# Prom21Core.net
KiCad netlist of a schematic drawn in Altium Designer
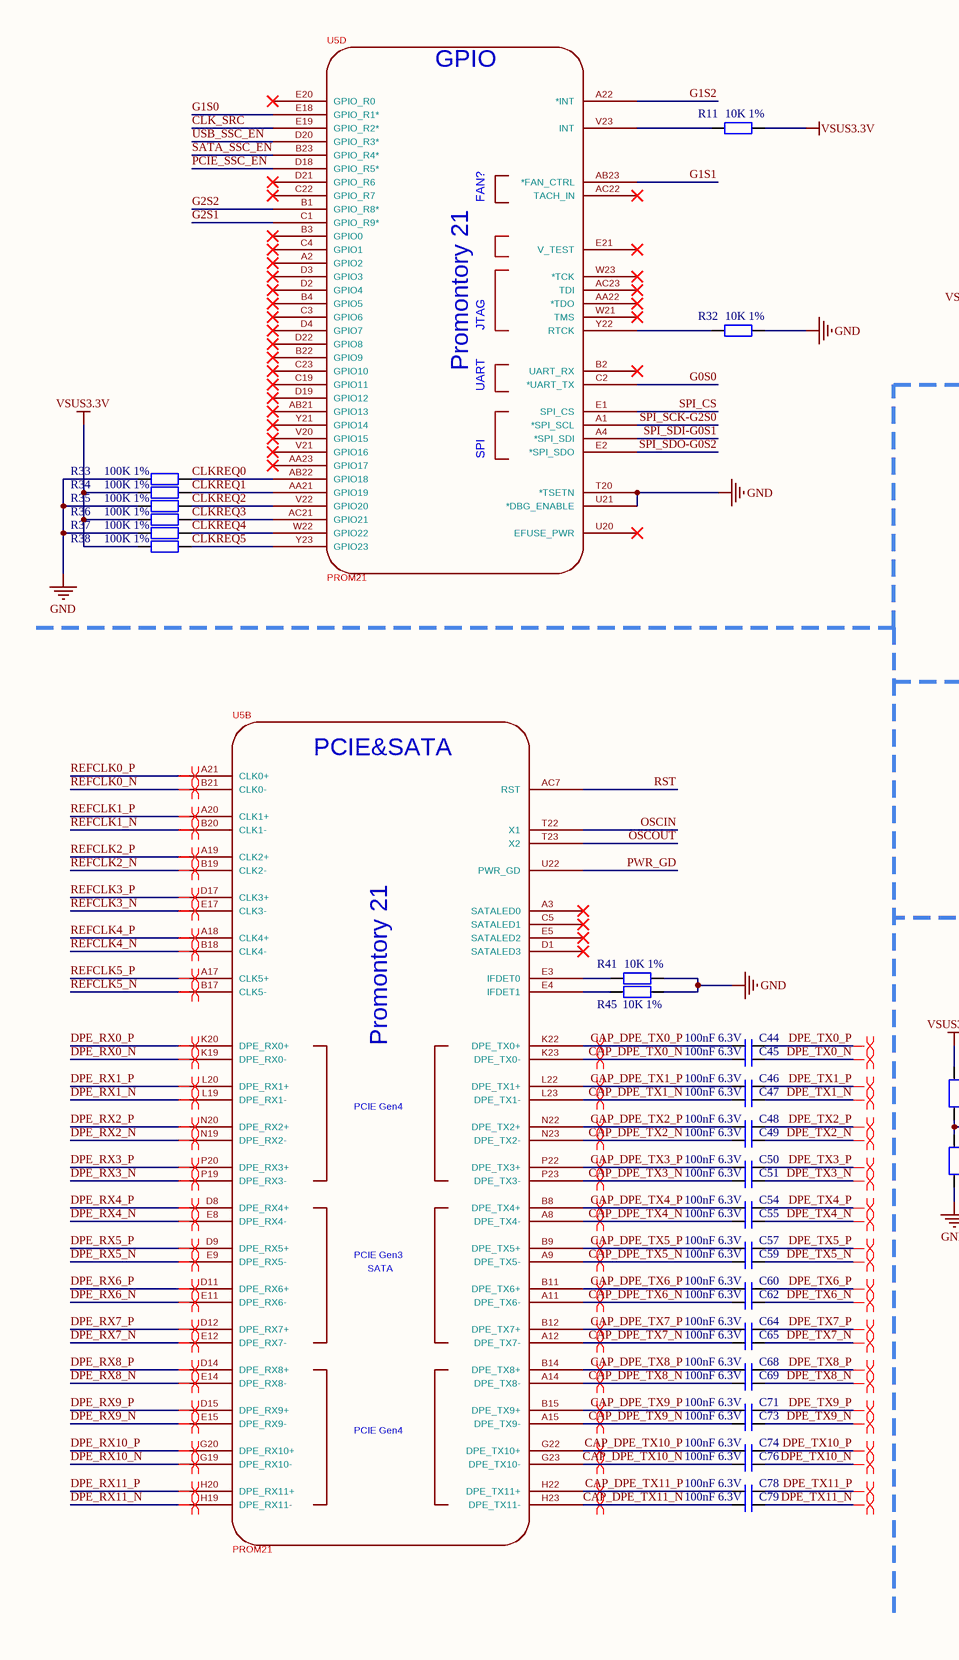
[diagram p0: Prom21Core.SchDoc, left]
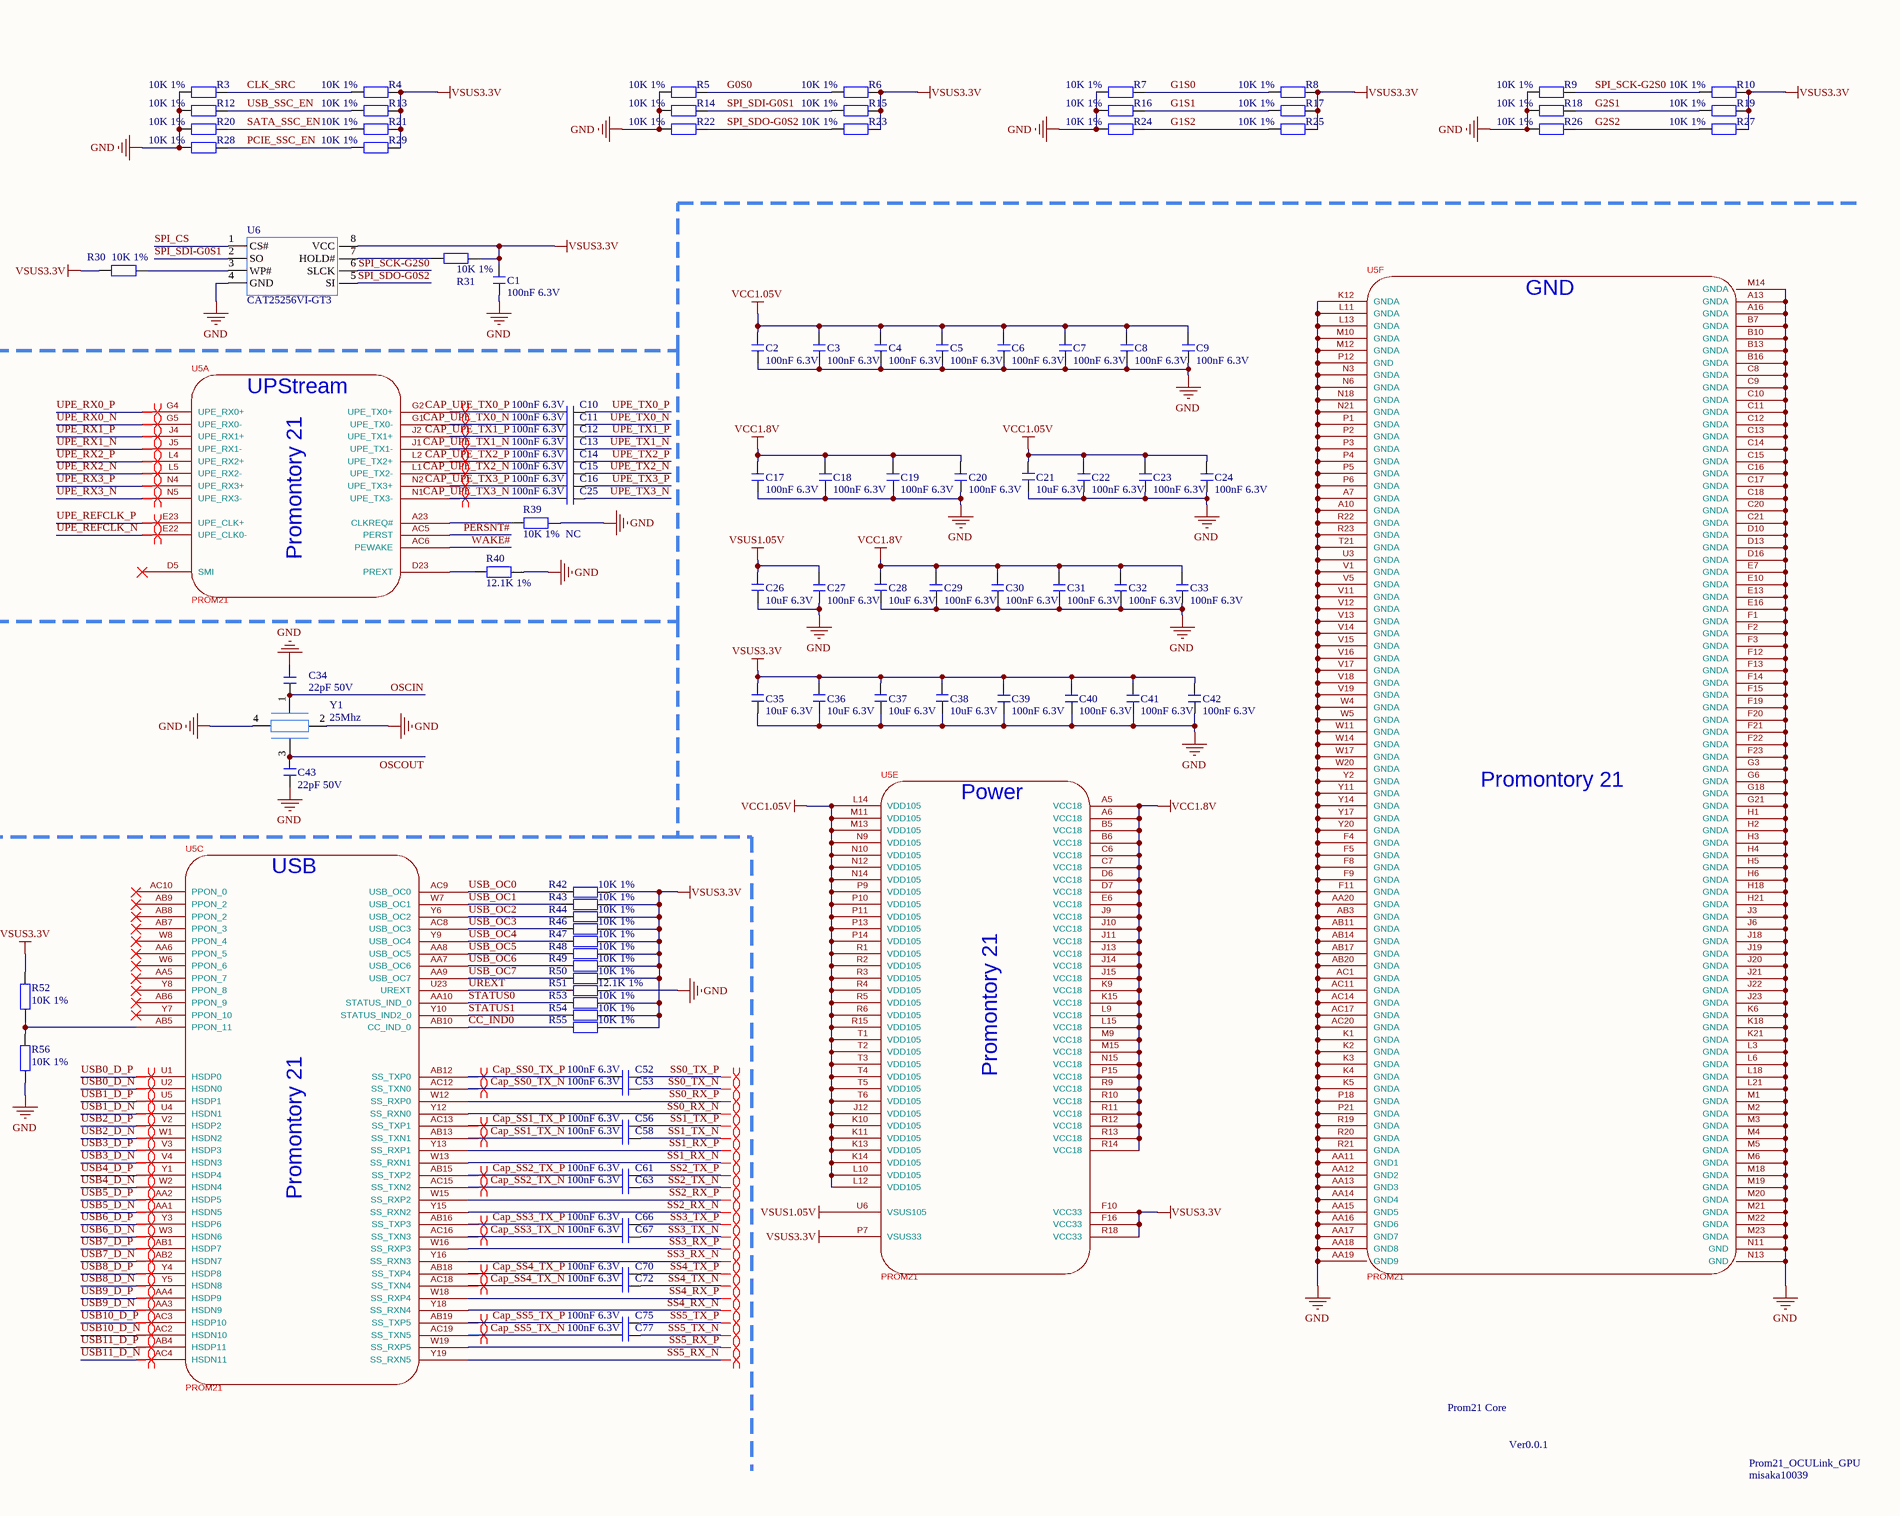
[diagram p1: Prom21Core.SchDoc, right]

(export (version "E")
  (design (tool "Eeschema 10.0.6"))
  (components
    (comp (ref "C1")
      (value "100nF 6.3V")
      (footprint "C0402_L")
      (description "无极性贴片电容")
      (fields (field (name "版权归属") "源创客"))
      (libsource (lib "Capacitor") (part "C"))
    )
    (comp (ref "C2")
      (value "100nF 6.3V")
      (footprint "C0402_L")
      (description "无极性贴片电容")
      (fields (field (name "版权归属") "源创客"))
      (libsource (lib "Capacitor") (part "C"))
    )
    (comp (ref "C3")
      (value "100nF 6.3V")
      (footprint "C0402_L")
      (description "无极性贴片电容")
      (fields (field (name "版权归属") "源创客"))
      (libsource (lib "Capacitor") (part "C"))
    )
    (comp (ref "C4")
      (value "100nF 6.3V")
      (footprint "C0402_L")
      (description "无极性贴片电容")
      (fields (field (name "版权归属") "源创客"))
      (libsource (lib "Capacitor") (part "C"))
    )
    (comp (ref "C5")
      (value "100nF 6.3V")
      (footprint "C0402_L")
      (description "无极性贴片电容")
      (fields (field (name "版权归属") "源创客"))
      (libsource (lib "Capacitor") (part "C"))
    )
    (comp (ref "C6")
      (value "100nF 6.3V")
      (footprint "C0402_L")
      (description "无极性贴片电容")
      (fields (field (name "版权归属") "源创客"))
      (libsource (lib "Capacitor") (part "C"))
    )
    (comp (ref "C7")
      (value "100nF 6.3V")
      (footprint "C0402_L")
      (description "无极性贴片电容")
      (fields (field (name "版权归属") "源创客"))
      (libsource (lib "Capacitor") (part "C"))
    )
    (comp (ref "C8")
      (value "100nF 6.3V")
      (footprint "C0402_L")
      (description "无极性贴片电容")
      (fields (field (name "版权归属") "源创客"))
      (libsource (lib "Capacitor") (part "C"))
    )
    (comp (ref "C9")
      (value "100nF 6.3V")
      (footprint "C0402_L")
      (description "无极性贴片电容")
      (fields (field (name "版权归属") "源创客"))
      (libsource (lib "Capacitor") (part "C"))
    )
    (comp (ref "C10")
      (value "100nF 6.3V")
      (footprint "C0402_L")
      (description "无极性贴片电容")
      (fields (field (name "版权归属") "源创客"))
      (libsource (lib "Capacitor") (part "C"))
    )
    (comp (ref "C11")
      (value "100nF 6.3V")
      (footprint "C0402_L")
      (description "无极性贴片电容")
      (fields (field (name "版权归属") "源创客"))
      (libsource (lib "Capacitor") (part "C"))
    )
    (comp (ref "C12")
      (value "100nF 6.3V")
      (footprint "C0402_L")
      (description "无极性贴片电容")
      (fields (field (name "版权归属") "源创客"))
      (libsource (lib "Capacitor") (part "C"))
    )
    (comp (ref "C13")
      (value "100nF 6.3V")
      (footprint "C0402_L")
      (description "无极性贴片电容")
      (fields (field (name "版权归属") "源创客"))
      (libsource (lib "Capacitor") (part "C"))
    )
    (comp (ref "C14")
      (value "100nF 6.3V")
      (footprint "C0402_L")
      (description "无极性贴片电容")
      (fields (field (name "版权归属") "源创客"))
      (libsource (lib "Capacitor") (part "C"))
    )
    (comp (ref "C15")
      (value "100nF 6.3V")
      (footprint "C0402_L")
      (description "无极性贴片电容")
      (fields (field (name "版权归属") "源创客"))
      (libsource (lib "Capacitor") (part "C"))
    )
    (comp (ref "C16")
      (value "100nF 6.3V")
      (footprint "C0402_L")
      (description "无极性贴片电容")
      (fields (field (name "版权归属") "源创客"))
      (libsource (lib "Capacitor") (part "C"))
    )
    (comp (ref "C17")
      (value "100nF 6.3V")
      (footprint "C0402_L")
      (description "无极性贴片电容")
      (fields (field (name "版权归属") "源创客"))
      (libsource (lib "Capacitor") (part "C"))
    )
    (comp (ref "C18")
      (value "100nF 6.3V")
      (footprint "C0402_L")
      (description "无极性贴片电容")
      (fields (field (name "版权归属") "源创客"))
      (libsource (lib "Capacitor") (part "C"))
    )
    (comp (ref "C19")
      (value "100nF 6.3V")
      (footprint "C0402_L")
      (description "无极性贴片电容")
      (fields (field (name "版权归属") "源创客"))
      (libsource (lib "Capacitor") (part "C"))
    )
    (comp (ref "C20")
      (value "100nF 6.3V")
      (footprint "C0402_L")
      (description "无极性贴片电容")
      (fields (field (name "版权归属") "源创客"))
      (libsource (lib "Capacitor") (part "C"))
    )
    (comp (ref "C21")
      (value "10uF 6.3V")
      (footprint "C0603_L")
      (description "无极性贴片电容")
      (fields (field (name "版权归属") "源创客"))
      (libsource (lib "Capacitor") (part "C"))
    )
    (comp (ref "C22")
      (value "100nF 6.3V")
      (footprint "C0402_L")
      (description "无极性贴片电容")
      (fields (field (name "版权归属") "源创客"))
      (libsource (lib "Capacitor") (part "C"))
    )
    (comp (ref "C23")
      (value "100nF 6.3V")
      (footprint "C0402_L")
      (description "无极性贴片电容")
      (fields (field (name "版权归属") "源创客"))
      (libsource (lib "Capacitor") (part "C"))
    )
    (comp (ref "C24")
      (value "100nF 6.3V")
      (footprint "C0402_L")
      (description "无极性贴片电容")
      (fields (field (name "版权归属") "源创客"))
      (libsource (lib "Capacitor") (part "C"))
    )
    (comp (ref "C25")
      (value "100nF 6.3V")
      (footprint "C0402_L")
      (description "无极性贴片电容")
      (fields (field (name "版权归属") "源创客"))
      (libsource (lib "Capacitor") (part "C"))
    )
    (comp (ref "C26")
      (value "10uF 6.3V")
      (footprint "C0603_L")
      (description "无极性贴片电容")
      (fields (field (name "版权归属") "源创客"))
      (libsource (lib "Capacitor") (part "C"))
    )
    (comp (ref "C27")
      (value "100nF 6.3V")
      (footprint "C0402_L")
      (description "无极性贴片电容")
      (fields (field (name "版权归属") "源创客"))
      (libsource (lib "Capacitor") (part "C"))
    )
    (comp (ref "C28")
      (value "10uF 6.3V")
      (footprint "C0603_L")
      (description "无极性贴片电容")
      (fields (field (name "版权归属") "源创客"))
      (libsource (lib "Capacitor") (part "C"))
    )
    (comp (ref "C29")
      (value "100nF 6.3V")
      (footprint "C0402_L")
      (description "无极性贴片电容")
      (fields (field (name "版权归属") "源创客"))
      (libsource (lib "Capacitor") (part "C"))
    )
    (comp (ref "C30")
      (value "100nF 6.3V")
      (footprint "C0402_L")
      (description "无极性贴片电容")
      (fields (field (name "版权归属") "源创客"))
      (libsource (lib "Capacitor") (part "C"))
    )
    (comp (ref "C31")
      (value "100nF 6.3V")
      (footprint "C0402_L")
      (description "无极性贴片电容")
      (fields (field (name "版权归属") "源创客"))
      (libsource (lib "Capacitor") (part "C"))
    )
    (comp (ref "C32")
      (value "100nF 6.3V")
      (footprint "C0402_L")
      (description "无极性贴片电容")
      (fields (field (name "版权归属") "源创客"))
      (libsource (lib "Capacitor") (part "C"))
    )
    (comp (ref "C33")
      (value "100nF 6.3V")
      (footprint "C0402_L")
      (description "无极性贴片电容")
      (fields (field (name "版权归属") "源创客"))
      (libsource (lib "Capacitor") (part "C"))
    )
    (comp (ref "C34")
      (value "22pF 50V")
      (footprint "C0402_L")
      (description "无极性贴片电容")
      (fields (field (name "版权归属") "源创客"))
      (libsource (lib "Capacitor") (part "C"))
    )
    (comp (ref "C35")
      (value "10uF 6.3V")
      (footprint "C0603_L")
      (description "无极性贴片电容")
      (fields (field (name "版权归属") "源创客"))
      (libsource (lib "Capacitor") (part "C"))
    )
    (comp (ref "C36")
      (value "10uF 6.3V")
      (footprint "C0603_L")
      (description "无极性贴片电容")
      (fields (field (name "版权归属") "源创客"))
      (libsource (lib "Capacitor") (part "C"))
    )
    (comp (ref "C37")
      (value "10uF 6.3V")
      (footprint "C0603_L")
      (description "无极性贴片电容")
      (fields (field (name "版权归属") "源创客"))
      (libsource (lib "Capacitor") (part "C"))
    )
    (comp (ref "C38")
      (value "10uF 6.3V")
      (footprint "C0603_L")
      (description "无极性贴片电容")
      (fields (field (name "版权归属") "源创客"))
      (libsource (lib "Capacitor") (part "C"))
    )
    (comp (ref "C39")
      (value "100nF 6.3V")
      (footprint "C0402_L")
      (description "无极性贴片电容")
      (fields (field (name "版权归属") "源创客"))
      (libsource (lib "Capacitor") (part "C"))
    )
    (comp (ref "C40")
      (value "100nF 6.3V")
      (footprint "C0402_L")
      (description "无极性贴片电容")
      (fields (field (name "版权归属") "源创客"))
      (libsource (lib "Capacitor") (part "C"))
    )
    (comp (ref "C41")
      (value "100nF 6.3V")
      (footprint "C0402_L")
      (description "无极性贴片电容")
      (fields (field (name "版权归属") "源创客"))
      (libsource (lib "Capacitor") (part "C"))
    )
    (comp (ref "C42")
      (value "100nF 6.3V")
      (footprint "C0402_L")
      (description "无极性贴片电容")
      (fields (field (name "版权归属") "源创客"))
      (libsource (lib "Capacitor") (part "C"))
    )
    (comp (ref "C43")
      (value "22pF 50V")
      (footprint "C0402_L")
      (description "无极性贴片电容")
      (fields (field (name "版权归属") "源创客"))
      (libsource (lib "Capacitor") (part "C"))
    )
    (comp (ref "C44")
      (value "100nF 6.3V")
      (footprint "C0402_L")
      (description "无极性贴片电容")
      (fields (field (name "版权归属") "源创客"))
      (libsource (lib "Capacitor") (part "C"))
    )
    (comp (ref "C45")
      (value "100nF 6.3V")
      (footprint "C0402_L")
      (description "无极性贴片电容")
      (fields (field (name "版权归属") "源创客"))
      (libsource (lib "Capacitor") (part "C"))
    )
    (comp (ref "C46")
      (value "100nF 6.3V")
      (footprint "C0402_L")
      (description "无极性贴片电容")
      (fields (field (name "版权归属") "源创客"))
      (libsource (lib "Capacitor") (part "C"))
    )
    (comp (ref "C47")
      (value "100nF 6.3V")
      (footprint "C0402_L")
      (description "无极性贴片电容")
      (fields (field (name "版权归属") "源创客"))
      (libsource (lib "Capacitor") (part "C"))
    )
    (comp (ref "C48")
      (value "100nF 6.3V")
      (footprint "C0402_L")
      (description "无极性贴片电容")
      (fields (field (name "版权归属") "源创客"))
      (libsource (lib "Capacitor") (part "C"))
    )
    (comp (ref "C49")
      (value "100nF 6.3V")
      (footprint "C0402_L")
      (description "无极性贴片电容")
      (fields (field (name "版权归属") "源创客"))
      (libsource (lib "Capacitor") (part "C"))
    )
    (comp (ref "C50")
      (value "100nF 6.3V")
      (footprint "C0402_L")
      (description "无极性贴片电容")
      (fields (field (name "版权归属") "源创客"))
      (libsource (lib "Capacitor") (part "C"))
    )
    (comp (ref "C51")
      (value "100nF 6.3V")
      (footprint "C0402_L")
      (description "无极性贴片电容")
      (fields (field (name "版权归属") "源创客"))
      (libsource (lib "Capacitor") (part "C"))
    )
    (comp (ref "C52")
      (value "100nF 6.3V")
      (footprint "C0402_L")
      (description "无极性贴片电容")
      (fields (field (name "版权归属") "源创客"))
      (libsource (lib "Capacitor") (part "C"))
    )
    (comp (ref "C53")
      (value "100nF 6.3V")
      (footprint "C0402_L")
      (description "无极性贴片电容")
      (fields (field (name "版权归属") "源创客"))
      (libsource (lib "Capacitor") (part "C"))
    )
    (comp (ref "C54")
      (value "100nF 6.3V")
      (footprint "C0402_L")
      (description "无极性贴片电容")
      (fields (field (name "版权归属") "源创客"))
      (libsource (lib "Capacitor") (part "C"))
    )
    (comp (ref "C55")
      (value "100nF 6.3V")
      (footprint "C0402_L")
      (description "无极性贴片电容")
      (fields (field (name "版权归属") "源创客"))
      (libsource (lib "Capacitor") (part "C"))
    )
    (comp (ref "C56")
      (value "100nF 6.3V")
      (footprint "C0402_L")
      (description "无极性贴片电容")
      (fields (field (name "版权归属") "源创客"))
      (libsource (lib "Capacitor") (part "C"))
    )
    (comp (ref "C57")
      (value "100nF 6.3V")
      (footprint "C0402_L")
      (description "无极性贴片电容")
      (fields (field (name "版权归属") "源创客"))
      (libsource (lib "Capacitor") (part "C"))
    )
    (comp (ref "C58")
      (value "100nF 6.3V")
      (footprint "C0402_L")
      (description "无极性贴片电容")
      (fields (field (name "版权归属") "源创客"))
      (libsource (lib "Capacitor") (part "C"))
    )
    (comp (ref "C59")
      (value "100nF 6.3V")
      (footprint "C0402_L")
      (description "无极性贴片电容")
      (fields (field (name "版权归属") "源创客"))
      (libsource (lib "Capacitor") (part "C"))
    )
    (comp (ref "C60")
      (value "100nF 6.3V")
      (footprint "C0402_L")
      (description "无极性贴片电容")
      (fields (field (name "版权归属") "源创客"))
      (libsource (lib "Capacitor") (part "C"))
    )
    (comp (ref "C61")
      (value "100nF 6.3V")
      (footprint "C0402_L")
      (description "无极性贴片电容")
      (fields (field (name "版权归属") "源创客"))
      (libsource (lib "Capacitor") (part "C"))
    )
    (comp (ref "C62")
      (value "100nF 6.3V")
      (footprint "C0402_L")
      (description "无极性贴片电容")
      (fields (field (name "版权归属") "源创客"))
      (libsource (lib "Capacitor") (part "C"))
    )
    (comp (ref "C63")
      (value "100nF 6.3V")
      (footprint "C0402_L")
      (description "无极性贴片电容")
      (fields (field (name "版权归属") "源创客"))
      (libsource (lib "Capacitor") (part "C"))
    )
    (comp (ref "C64")
      (value "100nF 6.3V")
      (footprint "C0402_L")
      (description "无极性贴片电容")
      (fields (field (name "版权归属") "源创客"))
      (libsource (lib "Capacitor") (part "C"))
    )
    (comp (ref "C65")
      (value "100nF 6.3V")
      (footprint "C0402_L")
      (description "无极性贴片电容")
      (fields (field (name "版权归属") "源创客"))
      (libsource (lib "Capacitor") (part "C"))
    )
    (comp (ref "C66")
      (value "100nF 6.3V")
      (footprint "C0402_L")
      (description "无极性贴片电容")
      (fields (field (name "版权归属") "源创客"))
      (libsource (lib "Capacitor") (part "C"))
    )
    (comp (ref "C67")
      (value "100nF 6.3V")
      (footprint "C0402_L")
      (description "无极性贴片电容")
      (fields (field (name "版权归属") "源创客"))
      (libsource (lib "Capacitor") (part "C"))
    )
    (comp (ref "C68")
      (value "100nF 6.3V")
      (footprint "C0402_L")
      (description "无极性贴片电容")
      (fields (field (name "版权归属") "源创客"))
      (libsource (lib "Capacitor") (part "C"))
    )
    (comp (ref "C69")
      (value "100nF 6.3V")
      (footprint "C0402_L")
      (description "无极性贴片电容")
      (fields (field (name "版权归属") "源创客"))
      (libsource (lib "Capacitor") (part "C"))
    )
    (comp (ref "C70")
      (value "100nF 6.3V")
      (footprint "C0402_L")
      (description "无极性贴片电容")
      (fields (field (name "版权归属") "源创客"))
      (libsource (lib "Capacitor") (part "C"))
    )
    (comp (ref "C71")
      (value "100nF 6.3V")
      (footprint "C0402_L")
      (description "无极性贴片电容")
      (fields (field (name "版权归属") "源创客"))
      (libsource (lib "Capacitor") (part "C"))
    )
    (comp (ref "C72")
      (value "100nF 6.3V")
      (footprint "C0402_L")
      (description "无极性贴片电容")
      (fields (field (name "版权归属") "源创客"))
      (libsource (lib "Capacitor") (part "C"))
    )
    (comp (ref "C73")
      (value "100nF 6.3V")
      (footprint "C0402_L")
      (description "无极性贴片电容")
      (fields (field (name "版权归属") "源创客"))
      (libsource (lib "Capacitor") (part "C"))
    )
    (comp (ref "C74")
      (value "100nF 6.3V")
      (footprint "C0402_L")
      (description "无极性贴片电容")
      (fields (field (name "版权归属") "源创客"))
      (libsource (lib "Capacitor") (part "C"))
    )
    (comp (ref "C75")
      (value "100nF 6.3V")
      (footprint "C0402_L")
      (description "无极性贴片电容")
      (fields (field (name "版权归属") "源创客"))
      (libsource (lib "Capacitor") (part "C"))
    )
    (comp (ref "C76")
      (value "100nF 6.3V")
      (footprint "C0402_L")
      (description "无极性贴片电容")
      (fields (field (name "版权归属") "源创客"))
      (libsource (lib "Capacitor") (part "C"))
    )
    (comp (ref "C77")
      (value "100nF 6.3V")
      (footprint "C0402_L")
      (description "无极性贴片电容")
      (fields (field (name "版权归属") "源创客"))
      (libsource (lib "Capacitor") (part "C"))
    )
    (comp (ref "C78")
      (value "100nF 6.3V")
      (footprint "C0402_L")
      (description "无极性贴片电容")
      (fields (field (name "版权归属") "源创客"))
      (libsource (lib "Capacitor") (part "C"))
    )
    (comp (ref "C79")
      (value "100nF 6.3V")
      (footprint "C0402_L")
      (description "无极性贴片电容")
      (fields (field (name "版权归属") "源创客"))
      (libsource (lib "Capacitor") (part "C"))
    )
    (comp (ref "R3")
      (value "10K 1%")
      (footprint "R0402_L")
      (description "贴片电阻")
      (fields (field (name "版权归属") "源创客"))
      (libsource (lib "Resistor") (part "R"))
    )
    (comp (ref "R4")
      (value "10K 1%")
      (footprint "R0402_L")
      (description "贴片电阻")
      (fields (field (name "版权归属") "源创客"))
      (libsource (lib "Resistor") (part "R"))
    )
    (comp (ref "R5")
      (value "10K 1%")
      (footprint "R0402_L")
      (description "贴片电阻")
      (fields (field (name "版权归属") "源创客"))
      (libsource (lib "Resistor") (part "R"))
    )
    (comp (ref "R6")
      (value "10K 1%")
      (footprint "R0402_L")
      (description "贴片电阻")
      (fields (field (name "版权归属") "源创客"))
      (libsource (lib "Resistor") (part "R"))
    )
    (comp (ref "R7")
      (value "10K 1%")
      (footprint "R0402_L")
      (description "贴片电阻")
      (fields (field (name "版权归属") "源创客"))
      (libsource (lib "Resistor") (part "R"))
    )
    (comp (ref "R8")
      (value "10K 1%")
      (footprint "R0402_L")
      (description "贴片电阻")
      (fields (field (name "版权归属") "源创客"))
      (libsource (lib "Resistor") (part "R"))
    )
    (comp (ref "R9")
      (value "10K 1%")
      (footprint "R0402_L")
      (description "贴片电阻")
      (fields (field (name "版权归属") "源创客"))
      (libsource (lib "Resistor") (part "R"))
    )
    (comp (ref "R10")
      (value "10K 1%")
      (footprint "R0402_L")
      (description "贴片电阻")
      (fields (field (name "版权归属") "源创客"))
      (libsource (lib "Resistor") (part "R"))
    )
    (comp (ref "R11")
      (value "10K 1%")
      (footprint "R0402_L")
      (description "贴片电阻")
      (fields (field (name "版权归属") "源创客"))
      (libsource (lib "Resistor") (part "R"))
    )
    (comp (ref "R12")
      (value "10K 1%")
      (footprint "R0402_L")
      (description "贴片电阻")
      (fields (field (name "版权归属") "源创客"))
      (libsource (lib "Resistor") (part "R"))
    )
    (comp (ref "R13")
      (value "10K 1%")
      (footprint "R0402_L")
      (description "贴片电阻")
      (fields (field (name "版权归属") "源创客"))
      (libsource (lib "Resistor") (part "R"))
    )
    (comp (ref "R14")
      (value "10K 1%")
      (footprint "R0402_L")
      (description "贴片电阻")
      (fields (field (name "版权归属") "源创客"))
      (libsource (lib "Resistor") (part "R"))
    )
    (comp (ref "R15")
      (value "10K 1%")
      (footprint "R0402_L")
      (description "贴片电阻")
      (fields (field (name "版权归属") "源创客"))
      (libsource (lib "Resistor") (part "R"))
    )
    (comp (ref "R16")
      (value "10K 1%")
      (footprint "R0402_L")
      (description "贴片电阻")
      (fields (field (name "版权归属") "源创客"))
      (libsource (lib "Resistor") (part "R"))
    )
    (comp (ref "R17")
      (value "10K 1%")
      (footprint "R0402_L")
      (description "贴片电阻")
      (fields (field (name "版权归属") "源创客"))
      (libsource (lib "Resistor") (part "R"))
    )
    (comp (ref "R18")
      (value "10K 1%")
      (footprint "R0402_L")
      (description "贴片电阻")
      (fields (field (name "版权归属") "源创客"))
      (libsource (lib "Resistor") (part "R"))
    )
    (comp (ref "R19")
      (value "10K 1%")
      (footprint "R0402_L")
      (description "贴片电阻")
      (fields (field (name "版权归属") "源创客"))
      (libsource (lib "Resistor") (part "R"))
    )
    (comp (ref "R20")
      (value "10K 1%")
      (footprint "R0402_L")
      (description "贴片电阻")
      (fields (field (name "版权归属") "源创客"))
      (libsource (lib "Resistor") (part "R"))
    )
    (comp (ref "R21")
      (value "10K 1%")
      (footprint "R0402_L")
      (description "贴片电阻")
      (fields (field (name "版权归属") "源创客"))
      (libsource (lib "Resistor") (part "R"))
    )
    (comp (ref "R22")
      (value "10K 1%")
      (footprint "R0402_L")
      (description "贴片电阻")
      (fields (field (name "版权归属") "源创客"))
      (libsource (lib "Resistor") (part "R"))
    )
    (comp (ref "R23")
      (value "10K 1%")
      (footprint "R0402_L")
      (description "贴片电阻")
      (fields (field (name "版权归属") "源创客"))
      (libsource (lib "Resistor") (part "R"))
    )
    (comp (ref "R24")
      (value "10K 1%")
      (footprint "R0402_L")
      (description "贴片电阻")
      (fields (field (name "版权归属") "源创客"))
      (libsource (lib "Resistor") (part "R"))
    )
    (comp (ref "R25")
      (value "10K 1%")
      (footprint "R0402_L")
      (description "贴片电阻")
      (fields (field (name "版权归属") "源创客"))
      (libsource (lib "Resistor") (part "R"))
    )
    (comp (ref "R26")
      (value "10K 1%")
      (footprint "R0402_L")
      (description "贴片电阻")
      (fields (field (name "版权归属") "源创客"))
      (libsource (lib "Resistor") (part "R"))
    )
    (comp (ref "R27")
      (value "10K 1%")
      (footprint "R0402_L")
      (description "贴片电阻")
      (fields (field (name "版权归属") "源创客"))
      (libsource (lib "Resistor") (part "R"))
    )
    (comp (ref "R28")
      (value "10K 1%")
      (footprint "R0402_L")
      (description "贴片电阻")
      (fields (field (name "版权归属") "源创客"))
      (libsource (lib "Resistor") (part "R"))
    )
    (comp (ref "R29")
      (value "10K 1%")
      (footprint "R0402_L")
      (description "贴片电阻")
      (fields (field (name "版权归属") "源创客"))
      (libsource (lib "Resistor") (part "R"))
    )
    (comp (ref "R30")
      (value "10K 1%")
      (footprint "R0402_L")
      (description "贴片电阻")
      (fields (field (name "版权归属") "源创客"))
      (libsource (lib "Resistor") (part "R"))
    )
    (comp (ref "R31")
      (value "10K 1%")
      (footprint "R0402_L")
      (description "贴片电阻")
      (fields (field (name "版权归属") "源创客"))
      (libsource (lib "Resistor") (part "R"))
    )
    (comp (ref "R32")
      (value "10K 1%")
      (footprint "R0402_L")
      (description "贴片电阻")
      (fields (field (name "版权归属") "源创客"))
      (libsource (lib "Resistor") (part "R"))
    )
    (comp (ref "R33")
      (value "100K 1%")
      (footprint "R0402_L")
      (description "贴片电阻")
      (fields (field (name "版权归属") "源创客"))
      (libsource (lib "Resistor") (part "R"))
    )
    (comp (ref "R34")
      (value "100K 1%")
      (footprint "R0402_L")
      (description "贴片电阻")
      (fields (field (name "版权归属") "源创客"))
      (libsource (lib "Resistor") (part "R"))
    )
    (comp (ref "R35")
      (value "100K 1%")
      (footprint "R0402_L")
      (description "贴片电阻")
      (fields (field (name "版权归属") "源创客"))
      (libsource (lib "Resistor") (part "R"))
    )
    (comp (ref "R36")
      (value "100K 1%")
      (footprint "R0402_L")
      (description "贴片电阻")
      (fields (field (name "版权归属") "源创客"))
      (libsource (lib "Resistor") (part "R"))
    )
    (comp (ref "R37")
      (value "100K 1%")
      (footprint "R0402_L")
      (description "贴片电阻")
      (fields (field (name "版权归属") "源创客"))
      (libsource (lib "Resistor") (part "R"))
    )
    (comp (ref "R38")
      (value "100K 1%")
      (footprint "R0402_L")
      (description "贴片电阻")
      (fields (field (name "版权归属") "源创客"))
      (libsource (lib "Resistor") (part "R"))
    )
    (comp (ref "R39")
      (value "10K 1%  NC")
      (footprint "R0402_L")
      (description "贴片电阻")
      (fields (field (name "版权归属") "源创客"))
      (libsource (lib "Resistor") (part "R"))
    )
    (comp (ref "R40")
      (value "12.1K 1%")
      (footprint "R0402_L")
      (description "贴片电阻")
      (fields (field (name "版权归属") "源创客"))
      (libsource (lib "Resistor") (part "R"))
    )
    (comp (ref "R41")
      (value "10K 1%")
      (footprint "R0402_L")
      (description "贴片电阻")
      (fields (field (name "版权归属") "源创客"))
      (libsource (lib "Resistor") (part "R"))
    )
    (comp (ref "R42")
      (value "10K 1%")
      (footprint "R0402_L")
      (description "贴片电阻")
      (fields (field (name "版权归属") "源创客"))
      (libsource (lib "Resistor") (part "R"))
    )
    (comp (ref "R43")
      (value "10K 1%")
      (footprint "R0402_L")
      (description "贴片电阻")
      (fields (field (name "版权归属") "源创客"))
      (libsource (lib "Resistor") (part "R"))
    )
    (comp (ref "R44")
      (value "10K 1%")
      (footprint "R0402_L")
      (description "贴片电阻")
      (fields (field (name "版权归属") "源创客"))
      (libsource (lib "Resistor") (part "R"))
    )
    (comp (ref "R45")
      (value "10K 1%")
      (footprint "R0402_L")
      (description "贴片电阻")
      (fields (field (name "版权归属") "源创客"))
      (libsource (lib "Resistor") (part "R"))
    )
    (comp (ref "R46")
      (value "10K 1%")
      (footprint "R0402_L")
      (description "贴片电阻")
      (fields (field (name "版权归属") "源创客"))
      (libsource (lib "Resistor") (part "R"))
    )
    (comp (ref "R47")
      (value "10K 1%")
      (footprint "R0402_L")
      (description "贴片电阻")
      (fields (field (name "版权归属") "源创客"))
      (libsource (lib "Resistor") (part "R"))
    )
    (comp (ref "R48")
      (value "10K 1%")
      (footprint "R0402_L")
      (description "贴片电阻")
      (fields (field (name "版权归属") "源创客"))
      (libsource (lib "Resistor") (part "R"))
    )
    (comp (ref "R49")
      (value "10K 1%")
      (footprint "R0402_L")
      (description "贴片电阻")
      (fields (field (name "版权归属") "源创客"))
      (libsource (lib "Resistor") (part "R"))
    )
    (comp (ref "R50")
      (value "10K 1%")
      (footprint "R0402_L")
      (description "贴片电阻")
      (fields (field (name "版权归属") "源创客"))
      (libsource (lib "Resistor") (part "R"))
    )
    (comp (ref "R51")
      (value "12.1K 1%")
      (footprint "R0402_L")
      (description "贴片电阻")
      (fields (field (name "版权归属") "源创客"))
      (libsource (lib "Resistor") (part "R"))
    )
    (comp (ref "R52")
      (value "10K 1%")
      (footprint "R0402_L")
      (description "贴片电阻")
      (fields (field (name "版权归属") "源创客"))
      (libsource (lib "Resistor") (part "R"))
    )
    (comp (ref "R53")
      (value "10K 1%")
      (footprint "R0402_L")
      (description "贴片电阻")
      (fields (field (name "版权归属") "源创客"))
      (libsource (lib "Resistor") (part "R"))
    )
    (comp (ref "R54")
      (value "10K 1%")
      (footprint "R0402_L")
      (description "贴片电阻")
      (fields (field (name "版权归属") "源创客"))
      (libsource (lib "Resistor") (part "R"))
    )
    (comp (ref "R55")
      (value "10K 1%")
      (footprint "R0402_L")
      (description "贴片电阻")
      (fields (field (name "版权归属") "源创客"))
      (libsource (lib "Resistor") (part "R"))
    )
    (comp (ref "R56")
      (value "10K 1%")
      (footprint "R0402_L")
      (description "贴片电阻")
      (fields (field (name "版权归属") "源创客"))
      (libsource (lib "Resistor") (part "R"))
    )
    (comp (ref "U5")
      (value "PROM21")
      (footprint "PROM21")
      (description "AMD B650")
      (libsource (lib "Brage") (part "PROM21"))
    )
    (comp (ref "U6") (value "CAT25256VI-GT3") (footprint "SOP8_M") (libsource (lib "Flash") (part "P25D40H")))
    (comp (ref "Y1") (value "25Mhz") (footprint "OSC-3225-4P") (libsource (lib "Crystal") (part "Crystal")))
  )
  (nets
    (net (code "1") (name "/CAP_DPE_TX0_N") (class "Default")
      (node (ref "C45") (pin "2") (pinfunction "2_2") (pintype "passive"))
      (node (ref "U5") (pin "K23") (pinfunction "DPE_TX0-_K23") (pintype "passive"))
    )
    (net (code "2") (name "/CAP_DPE_TX0_P") (class "Default")
      (node (ref "C44") (pin "2") (pinfunction "2_2") (pintype "passive"))
      (node (ref "U5") (pin "K22") (pinfunction "DPE_TX0+_K22") (pintype "passive"))
    )
    (net (code "3") (name "/CAP_DPE_TX1_N") (class "Default")
      (node (ref "C47") (pin "2") (pinfunction "2_2") (pintype "passive"))
      (node (ref "U5") (pin "L23") (pinfunction "DPE_TX1-_L23") (pintype "passive"))
    )
    (net (code "4") (name "/CAP_DPE_TX1_P") (class "Default")
      (node (ref "C46") (pin "2") (pinfunction "2_2") (pintype "passive"))
      (node (ref "U5") (pin "L22") (pinfunction "DPE_TX1+_L22") (pintype "passive"))
    )
    (net (code "5") (name "/CAP_DPE_TX2_N") (class "Default")
      (node (ref "C49") (pin "2") (pinfunction "2_2") (pintype "passive"))
      (node (ref "U5") (pin "N23") (pinfunction "DPE_TX2-_N23") (pintype "passive"))
    )
    (net (code "6") (name "/CAP_DPE_TX2_P") (class "Default")
      (node (ref "C48") (pin "2") (pinfunction "2_2") (pintype "passive"))
      (node (ref "U5") (pin "N22") (pinfunction "DPE_TX2+_N22") (pintype "passive"))
    )
    (net (code "7") (name "/CAP_DPE_TX3_N") (class "Default")
      (node (ref "C51") (pin "2") (pinfunction "2_2") (pintype "passive"))
      (node (ref "U5") (pin "P23") (pinfunction "DPE_TX3-_P23") (pintype "passive"))
    )
    (net (code "8") (name "/CAP_DPE_TX3_P") (class "Default")
      (node (ref "C50") (pin "2") (pinfunction "2_2") (pintype "passive"))
      (node (ref "U5") (pin "P22") (pinfunction "DPE_TX3+_P22") (pintype "passive"))
    )
    (net (code "9") (name "/CAP_DPE_TX4_N") (class "Default")
      (node (ref "C55") (pin "2") (pinfunction "2_2") (pintype "passive"))
      (node (ref "U5") (pin "A8") (pinfunction "DPE_TX4-_A8") (pintype "passive"))
    )
    (net (code "10") (name "/CAP_DPE_TX4_P") (class "Default")
      (node (ref "C54") (pin "2") (pinfunction "2_2") (pintype "passive"))
      (node (ref "U5") (pin "B8") (pinfunction "DPE_TX4+_B8") (pintype "passive"))
    )
    (net (code "11") (name "/CAP_DPE_TX5_N") (class "Default")
      (node (ref "C59") (pin "2") (pinfunction "2_2") (pintype "passive"))
      (node (ref "U5") (pin "A9") (pinfunction "DPE_TX5-_A9") (pintype "passive"))
    )
    (net (code "12") (name "/CAP_DPE_TX5_P") (class "Default")
      (node (ref "C57") (pin "2") (pinfunction "2_2") (pintype "passive"))
      (node (ref "U5") (pin "B9") (pinfunction "DPE_TX5+_B9") (pintype "passive"))
    )
    (net (code "13") (name "/CAP_DPE_TX6_N") (class "Default")
      (node (ref "C62") (pin "2") (pinfunction "2_2") (pintype "passive"))
      (node (ref "U5") (pin "A11") (pinfunction "DPE_TX6-_A11") (pintype "passive"))
    )
    (net (code "14") (name "/CAP_DPE_TX6_P") (class "Default")
      (node (ref "C60") (pin "2") (pinfunction "2_2") (pintype "passive"))
      (node (ref "U5") (pin "B11") (pinfunction "DPE_TX6+_B11") (pintype "passive"))
    )
    (net (code "15") (name "/CAP_DPE_TX7_N") (class "Default")
      (node (ref "C65") (pin "2") (pinfunction "2_2") (pintype "passive"))
      (node (ref "U5") (pin "A12") (pinfunction "DPE_TX7-_A12") (pintype "passive"))
    )
    (net (code "16") (name "/CAP_DPE_TX7_P") (class "Default")
      (node (ref "C64") (pin "2") (pinfunction "2_2") (pintype "passive"))
      (node (ref "U5") (pin "B12") (pinfunction "DPE_TX7+_B12") (pintype "passive"))
    )
    (net (code "17") (name "/CAP_DPE_TX8_N") (class "Default")
      (node (ref "C69") (pin "2") (pinfunction "2_2") (pintype "passive"))
      (node (ref "U5") (pin "A14") (pinfunction "DPE_TX8-_A14") (pintype "passive"))
    )
    (net (code "18") (name "/CAP_DPE_TX8_P") (class "Default")
      (node (ref "C68") (pin "2") (pinfunction "2_2") (pintype "passive"))
      (node (ref "U5") (pin "B14") (pinfunction "DPE_TX8+_B14") (pintype "passive"))
    )
    (net (code "19") (name "/CAP_DPE_TX9_N") (class "Default")
      (node (ref "C73") (pin "2") (pinfunction "2_2") (pintype "passive"))
      (node (ref "U5") (pin "A15") (pinfunction "DPE_TX9-_A15") (pintype "passive"))
    )
    (net (code "20") (name "/CAP_DPE_TX9_P") (class "Default")
      (node (ref "C71") (pin "2") (pinfunction "2_2") (pintype "passive"))
      (node (ref "U5") (pin "B15") (pinfunction "DPE_TX9+_B15") (pintype "passive"))
    )
    (net (code "21") (name "/CAP_DPE_TX10_N") (class "Default")
      (node (ref "C76") (pin "2") (pinfunction "2_2") (pintype "passive"))
      (node (ref "U5") (pin "G23") (pinfunction "DPE_TX10-_G23") (pintype "passive"))
    )
    (net (code "22") (name "/CAP_DPE_TX10_P") (class "Default")
      (node (ref "C74") (pin "2") (pinfunction "2_2") (pintype "passive"))
      (node (ref "U5") (pin "G22") (pinfunction "DPE_TX10+_G22") (pintype "passive"))
    )
    (net (code "23") (name "/CAP_DPE_TX11_N") (class "Default")
      (node (ref "C79") (pin "2") (pinfunction "2_2") (pintype "passive"))
      (node (ref "U5") (pin "H23") (pinfunction "DPE_TX11-_H23") (pintype "passive"))
    )
    (net (code "24") (name "/CAP_DPE_TX11_P") (class "Default")
      (node (ref "C78") (pin "2") (pinfunction "2_2") (pintype "passive"))
      (node (ref "U5") (pin "H22") (pinfunction "DPE_TX11+_H22") (pintype "passive"))
    )
    (net (code "25") (name "/CAP_UPE_TX0_N") (class "Default")
      (node (ref "C11") (pin "2") (pinfunction "2_2") (pintype "passive"))
      (node (ref "U5") (pin "G1") (pinfunction "UPE_TX0-_G1") (pintype "passive"))
    )
    (net (code "26") (name "/CAP_UPE_TX0_P") (class "Default")
      (node (ref "C10") (pin "2") (pinfunction "2_2") (pintype "passive"))
      (node (ref "U5") (pin "G2") (pinfunction "UPE_TX0+_G2") (pintype "passive"))
    )
    (net (code "27") (name "/CAP_UPE_TX1_N") (class "Default")
      (node (ref "C13") (pin "2") (pinfunction "2_2") (pintype "passive"))
      (node (ref "U5") (pin "J1") (pinfunction "UPE_TX1-_J1") (pintype "passive"))
    )
    (net (code "28") (name "/CAP_UPE_TX1_P") (class "Default")
      (node (ref "C12") (pin "2") (pinfunction "2_2") (pintype "passive"))
      (node (ref "U5") (pin "J2") (pinfunction "UPE_TX1+_J2") (pintype "passive"))
    )
    (net (code "29") (name "/CAP_UPE_TX2_N") (class "Default")
      (node (ref "C15") (pin "2") (pinfunction "2_2") (pintype "passive"))
      (node (ref "U5") (pin "L1") (pinfunction "UPE_TX2-_L1") (pintype "passive"))
    )
    (net (code "30") (name "/CAP_UPE_TX2_P") (class "Default")
      (node (ref "C14") (pin "2") (pinfunction "2_2") (pintype "passive"))
      (node (ref "U5") (pin "L2") (pinfunction "UPE_TX2+_L2") (pintype "passive"))
    )
    (net (code "31") (name "/CAP_UPE_TX3_N") (class "Default")
      (node (ref "C25") (pin "2") (pinfunction "2_2") (pintype "passive"))
      (node (ref "U5") (pin "N1") (pinfunction "UPE_TX3-_N1") (pintype "passive"))
    )
    (net (code "32") (name "/CAP_UPE_TX3_P") (class "Default")
      (node (ref "C16") (pin "2") (pinfunction "2_2") (pintype "passive"))
      (node (ref "U5") (pin "N2") (pinfunction "UPE_TX3+_N2") (pintype "passive"))
    )
    (net (code "33") (name "/CC_IND0") (class "Default")
      (node (ref "R55") (pin "2") (pinfunction "2_2") (pintype "passive"))
      (node (ref "U5") (pin "AB10") (pinfunction "CC_IND_0_AB10") (pintype "passive"))
    )
    (net (code "34") (name "/CLKREQ0") (class "Default")
      (node (ref "R33") (pin "2") (pinfunction "2_2") (pintype "passive"))
      (node (ref "U5") (pin "AB22") (pinfunction "GPIO18_AB22") (pintype "passive"))
    )
    (net (code "35") (name "/CLKREQ1") (class "Default")
      (node (ref "R34") (pin "2") (pinfunction "2_2") (pintype "passive"))
      (node (ref "U5") (pin "AA21") (pinfunction "GPIO19_AA21") (pintype "passive"))
    )
    (net (code "36") (name "/CLKREQ2") (class "Default")
      (node (ref "R35") (pin "2") (pinfunction "2_2") (pintype "passive"))
      (node (ref "U5") (pin "V22") (pinfunction "GPIO20_V22") (pintype "passive"))
    )
    (net (code "37") (name "/CLKREQ3") (class "Default")
      (node (ref "R36") (pin "2") (pinfunction "2_2") (pintype "passive"))
      (node (ref "U5") (pin "AC21") (pinfunction "GPIO21_AC21") (pintype "passive"))
    )
    (net (code "38") (name "/CLKREQ4") (class "Default")
      (node (ref "R37") (pin "2") (pinfunction "2_2") (pintype "passive"))
      (node (ref "U5") (pin "W22") (pinfunction "GPIO22_W22") (pintype "passive"))
    )
    (net (code "39") (name "/CLKREQ5") (class "Default")
      (node (ref "R38") (pin "2") (pinfunction "2_2") (pintype "passive"))
      (node (ref "U5") (pin "Y23") (pinfunction "GPIO23_Y23") (pintype "passive"))
    )
    (net (code "40") (name "/CLK_SRC") (class "Default")
      (node (ref "R3") (pin "2") (pinfunction "2_2") (pintype "passive"))
      (node (ref "R4") (pin "1") (pinfunction "1_1") (pintype "passive"))
      (node (ref "U5") (pin "E19") (pinfunction "GPIO_R2*_E19") (pintype "passive"))
    )
    (net (code "41") (name "/Cap_SS0_TX_N") (class "Default")
      (node (ref "C53") (pin "2") (pinfunction "2_2") (pintype "passive"))
      (node (ref "U5") (pin "AC12") (pinfunction "SS_TXN0_AC12") (pintype "passive"))
    )
    (net (code "42") (name "/Cap_SS0_TX_P") (class "Default")
      (node (ref "C52") (pin "2") (pinfunction "2_2") (pintype "passive"))
      (node (ref "U5") (pin "AB12") (pinfunction "SS_TXP0_AB12") (pintype "passive"))
    )
    (net (code "43") (name "/Cap_SS1_TX_N") (class "Default")
      (node (ref "C58") (pin "2") (pinfunction "2_2") (pintype "passive"))
      (node (ref "U5") (pin "AB13") (pinfunction "SS_TXN1_AB13") (pintype "passive"))
    )
    (net (code "44") (name "/Cap_SS1_TX_P") (class "Default")
      (node (ref "C56") (pin "2") (pinfunction "2_2") (pintype "passive"))
      (node (ref "U5") (pin "AC13") (pinfunction "SS_TXP1_AC13") (pintype "passive"))
    )
    (net (code "45") (name "/Cap_SS2_TX_N") (class "Default")
      (node (ref "C63") (pin "2") (pinfunction "2_2") (pintype "passive"))
      (node (ref "U5") (pin "AC15") (pinfunction "SS_TXN2_AC15") (pintype "passive"))
    )
    (net (code "46") (name "/Cap_SS2_TX_P") (class "Default")
      (node (ref "C61") (pin "2") (pinfunction "2_2") (pintype "passive"))
      (node (ref "U5") (pin "AB15") (pinfunction "SS_TXP2_AB15") (pintype "passive"))
    )
    (net (code "47") (name "/Cap_SS3_TX_N") (class "Default")
      (node (ref "C67") (pin "2") (pinfunction "2_2") (pintype "passive"))
      (node (ref "U5") (pin "AC16") (pinfunction "SS_TXN3_AC16") (pintype "passive"))
    )
    (net (code "48") (name "/Cap_SS3_TX_P") (class "Default")
      (node (ref "C66") (pin "2") (pinfunction "2_2") (pintype "passive"))
      (node (ref "U5") (pin "AB16") (pinfunction "SS_TXP3_AB16") (pintype "passive"))
    )
    (net (code "49") (name "/Cap_SS4_TX_N") (class "Default")
      (node (ref "C72") (pin "2") (pinfunction "2_2") (pintype "passive"))
      (node (ref "U5") (pin "AC18") (pinfunction "SS_TXN4_AC18") (pintype "passive"))
    )
    (net (code "50") (name "/Cap_SS4_TX_P") (class "Default")
      (node (ref "C70") (pin "2") (pinfunction "2_2") (pintype "passive"))
      (node (ref "U5") (pin "AB18") (pinfunction "SS_TXP4_AB18") (pintype "passive"))
    )
    (net (code "51") (name "/Cap_SS5_TX_N") (class "Default")
      (node (ref "C77") (pin "2") (pinfunction "2_2") (pintype "passive"))
      (node (ref "U5") (pin "AC19") (pinfunction "SS_TXN5_AC19") (pintype "passive"))
    )
    (net (code "52") (name "/Cap_SS5_TX_P") (class "Default")
      (node (ref "C75") (pin "2") (pinfunction "2_2") (pintype "passive"))
      (node (ref "U5") (pin "AB19") (pinfunction "SS_TXP5_AB19") (pintype "passive"))
    )
    (net (code "53") (name "/DPE_RX0_N") (class "Default")
      (node (ref "U5") (pin "K19") (pinfunction "DPE_RX0-_K19") (pintype "passive"))
    )
    (net (code "54") (name "/DPE_RX0_P") (class "Default")
      (node (ref "U5") (pin "K20") (pinfunction "DPE_RX0+_K20") (pintype "passive"))
    )
    (net (code "55") (name "/DPE_RX1_N") (class "Default")
      (node (ref "U5") (pin "L19") (pinfunction "DPE_RX1-_L19") (pintype "passive"))
    )
    (net (code "56") (name "/DPE_RX1_P") (class "Default")
      (node (ref "U5") (pin "L20") (pinfunction "DPE_RX1+_L20") (pintype "passive"))
    )
    (net (code "57") (name "/DPE_RX2_N") (class "Default")
      (node (ref "U5") (pin "N19") (pinfunction "DPE_RX2-_N19") (pintype "passive"))
    )
    (net (code "58") (name "/DPE_RX2_P") (class "Default")
      (node (ref "U5") (pin "N20") (pinfunction "DPE_RX2+_N20") (pintype "passive"))
    )
    (net (code "59") (name "/DPE_RX3_N") (class "Default")
      (node (ref "U5") (pin "P19") (pinfunction "DPE_RX3-_P19") (pintype "passive"))
    )
    (net (code "60") (name "/DPE_RX3_P") (class "Default")
      (node (ref "U5") (pin "P20") (pinfunction "DPE_RX3+_P20") (pintype "passive"))
    )
    (net (code "61") (name "/DPE_RX4_N") (class "Default")
      (node (ref "U5") (pin "E8") (pinfunction "DPE_RX4-_E8") (pintype "passive"))
    )
    (net (code "62") (name "/DPE_RX4_P") (class "Default")
      (node (ref "U5") (pin "D8") (pinfunction "DPE_RX4+_D8") (pintype "passive"))
    )
    (net (code "63") (name "/DPE_RX5_N") (class "Default")
      (node (ref "U5") (pin "E9") (pinfunction "DPE_RX5-_E9") (pintype "passive"))
    )
    (net (code "64") (name "/DPE_RX5_P") (class "Default")
      (node (ref "U5") (pin "D9") (pinfunction "DPE_RX5+_D9") (pintype "passive"))
    )
    (net (code "65") (name "/DPE_RX6_N") (class "Default")
      (node (ref "U5") (pin "E11") (pinfunction "DPE_RX6-_E11") (pintype "passive"))
    )
    (net (code "66") (name "/DPE_RX6_P") (class "Default")
      (node (ref "U5") (pin "D11") (pinfunction "DPE_RX6+_D11") (pintype "passive"))
    )
    (net (code "67") (name "/DPE_RX7_N") (class "Default")
      (node (ref "U5") (pin "E12") (pinfunction "DPE_RX7-_E12") (pintype "passive"))
    )
    (net (code "68") (name "/DPE_RX7_P") (class "Default")
      (node (ref "U5") (pin "D12") (pinfunction "DPE_RX7+_D12") (pintype "passive"))
    )
    (net (code "69") (name "/DPE_RX8_N") (class "Default")
      (node (ref "U5") (pin "E14") (pinfunction "DPE_RX8-_E14") (pintype "passive"))
    )
    (net (code "70") (name "/DPE_RX8_P") (class "Default")
      (node (ref "U5") (pin "D14") (pinfunction "DPE_RX8+_D14") (pintype "passive"))
    )
    (net (code "71") (name "/DPE_RX9_N") (class "Default")
      (node (ref "U5") (pin "E15") (pinfunction "DPE_RX9-_E15") (pintype "passive"))
    )
    (net (code "72") (name "/DPE_RX9_P") (class "Default")
      (node (ref "U5") (pin "D15") (pinfunction "DPE_RX9+_D15") (pintype "passive"))
    )
    (net (code "73") (name "/DPE_RX10_N") (class "Default")
      (node (ref "U5") (pin "G19") (pinfunction "DPE_RX10-_G19") (pintype "passive"))
    )
    (net (code "74") (name "/DPE_RX10_P") (class "Default")
      (node (ref "U5") (pin "G20") (pinfunction "DPE_RX10+_G20") (pintype "passive"))
    )
    (net (code "75") (name "/DPE_RX11_N") (class "Default")
      (node (ref "U5") (pin "H19") (pinfunction "DPE_RX11-_H19") (pintype "passive"))
    )
    (net (code "76") (name "/DPE_RX11_P") (class "Default")
      (node (ref "U5") (pin "H20") (pinfunction "DPE_RX11+_H20") (pintype "passive"))
    )
    (net (code "77") (name "/DPE_TX0_N") (class "Default")
      (node (ref "C45") (pin "1") (pinfunction "1_1") (pintype "passive"))
    )
    (net (code "78") (name "/DPE_TX0_P") (class "Default")
      (node (ref "C44") (pin "1") (pinfunction "1_1") (pintype "passive"))
    )
    (net (code "79") (name "/DPE_TX1_N") (class "Default")
      (node (ref "C47") (pin "1") (pinfunction "1_1") (pintype "passive"))
    )
    (net (code "80") (name "/DPE_TX1_P") (class "Default")
      (node (ref "C46") (pin "1") (pinfunction "1_1") (pintype "passive"))
    )
    (net (code "81") (name "/DPE_TX2_N") (class "Default")
      (node (ref "C49") (pin "1") (pinfunction "1_1") (pintype "passive"))
    )
    (net (code "82") (name "/DPE_TX2_P") (class "Default")
      (node (ref "C48") (pin "1") (pinfunction "1_1") (pintype "passive"))
    )
    (net (code "83") (name "/DPE_TX3_N") (class "Default")
      (node (ref "C51") (pin "1") (pinfunction "1_1") (pintype "passive"))
    )
    (net (code "84") (name "/DPE_TX3_P") (class "Default")
      (node (ref "C50") (pin "1") (pinfunction "1_1") (pintype "passive"))
    )
    (net (code "85") (name "/DPE_TX4_N") (class "Default")
      (node (ref "C55") (pin "1") (pinfunction "1_1") (pintype "passive"))
    )
    (net (code "86") (name "/DPE_TX4_P") (class "Default")
      (node (ref "C54") (pin "1") (pinfunction "1_1") (pintype "passive"))
    )
    (net (code "87") (name "/DPE_TX5_N") (class "Default")
      (node (ref "C59") (pin "1") (pinfunction "1_1") (pintype "passive"))
    )
    (net (code "88") (name "/DPE_TX5_P") (class "Default")
      (node (ref "C57") (pin "1") (pinfunction "1_1") (pintype "passive"))
    )
    (net (code "89") (name "/DPE_TX6_N") (class "Default")
      (node (ref "C62") (pin "1") (pinfunction "1_1") (pintype "passive"))
    )
    (net (code "90") (name "/DPE_TX6_P") (class "Default")
      (node (ref "C60") (pin "1") (pinfunction "1_1") (pintype "passive"))
    )
    (net (code "91") (name "/DPE_TX7_N") (class "Default")
      (node (ref "C65") (pin "1") (pinfunction "1_1") (pintype "passive"))
    )
    (net (code "92") (name "/DPE_TX7_P") (class "Default")
      (node (ref "C64") (pin "1") (pinfunction "1_1") (pintype "passive"))
    )
    (net (code "93") (name "/DPE_TX8_N") (class "Default")
      (node (ref "C69") (pin "1") (pinfunction "1_1") (pintype "passive"))
    )
    (net (code "94") (name "/DPE_TX8_P") (class "Default")
      (node (ref "C68") (pin "1") (pinfunction "1_1") (pintype "passive"))
    )
    (net (code "95") (name "/DPE_TX9_N") (class "Default")
      (node (ref "C73") (pin "1") (pinfunction "1_1") (pintype "passive"))
    )
    (net (code "96") (name "/DPE_TX9_P") (class "Default")
      (node (ref "C71") (pin "1") (pinfunction "1_1") (pintype "passive"))
    )
    (net (code "97") (name "/DPE_TX10_N") (class "Default")
      (node (ref "C76") (pin "1") (pinfunction "1_1") (pintype "passive"))
    )
    (net (code "98") (name "/DPE_TX10_P") (class "Default")
      (node (ref "C74") (pin "1") (pinfunction "1_1") (pintype "passive"))
    )
    (net (code "99") (name "/DPE_TX11_N") (class "Default")
      (node (ref "C79") (pin "1") (pinfunction "1_1") (pintype "passive"))
    )
    (net (code "100") (name "/DPE_TX11_P") (class "Default")
      (node (ref "C78") (pin "1") (pinfunction "1_1") (pintype "passive"))
    )
    (net (code "101") (name "/G0S0") (class "Default")
      (node (ref "R5") (pin "2") (pinfunction "2_2") (pintype "passive"))
      (node (ref "R6") (pin "1") (pinfunction "1_1") (pintype "passive"))
      (node (ref "U5") (pin "C2") (pinfunction "*UART_TX_C2") (pintype "passive"))
    )
    (net (code "102") (name "/G1S0") (class "Default")
      (node (ref "R7") (pin "2") (pinfunction "2_2") (pintype "passive"))
      (node (ref "R8") (pin "1") (pinfunction "1_1") (pintype "passive"))
      (node (ref "U5") (pin "E18") (pinfunction "GPIO_R1*_E18") (pintype "passive"))
    )
    (net (code "103") (name "/G1S1") (class "Default")
      (node (ref "R16") (pin "2") (pinfunction "2_2") (pintype "passive"))
      (node (ref "R17") (pin "1") (pinfunction "1_1") (pintype "passive"))
      (node (ref "U5") (pin "AB23") (pinfunction "*FAN_CTRL_AB23") (pintype "passive"))
    )
    (net (code "104") (name "/G1S2") (class "Default")
      (node (ref "R24") (pin "2") (pinfunction "2_2") (pintype "passive"))
      (node (ref "R25") (pin "1") (pinfunction "1_1") (pintype "passive"))
      (node (ref "U5") (pin "A22") (pinfunction "*INT_A22") (pintype "passive"))
    )
    (net (code "105") (name "/G2S1") (class "Default")
      (node (ref "R18") (pin "2") (pinfunction "2_2") (pintype "passive"))
      (node (ref "R19") (pin "1") (pinfunction "1_1") (pintype "passive"))
      (node (ref "U5") (pin "C1") (pinfunction "GPIO_R9*_C1") (pintype "passive"))
    )
    (net (code "106") (name "/G2S2") (class "Default")
      (node (ref "R26") (pin "2") (pinfunction "2_2") (pintype "passive"))
      (node (ref "R27") (pin "1") (pinfunction "1_1") (pintype "passive"))
      (node (ref "U5") (pin "B1") (pinfunction "GPIO_R8*_B1") (pintype "passive"))
    )
    (net (code "107") (name "/OSCIN") (class "Default")
      (node (ref "C34") (pin "2") (pinfunction "2_2") (pintype "passive"))
      (node (ref "U5") (pin "T22") (pinfunction "X1_T22") (pintype "passive"))
      (node (ref "Y1") (pin "1") (pinfunction "XTAL_N_1") (pintype "passive"))
    )
    (net (code "108") (name "/OSCOUT") (class "Default")
      (node (ref "C43") (pin "2") (pinfunction "2_2") (pintype "passive"))
      (node (ref "U5") (pin "T23") (pinfunction "X2_T23") (pintype "passive"))
      (node (ref "Y1") (pin "3") (pinfunction "XTAL_P_3") (pintype "passive"))
    )
    (net (code "109") (name "/PCIE_SSC_EN") (class "Default")
      (node (ref "R28") (pin "2") (pinfunction "2_2") (pintype "passive"))
      (node (ref "R29") (pin "1") (pinfunction "1_1") (pintype "passive"))
      (node (ref "U5") (pin "D18") (pinfunction "GPIO_R5*_D18") (pintype "passive"))
    )
    (net (code "110") (name "/PERSNT#") (class "Default")
      (node (ref "U5") (pin "AC5") (pinfunction "PERST_AC5") (pintype "passive"))
    )
    (net (code "111") (name "/PWR_GD") (class "Default")
      (node (ref "U5") (pin "U22") (pinfunction "PWR_GD_U22") (pintype "passive"))
    )
    (net (code "112") (name "/REFCLK0_N") (class "Default")
      (node (ref "U5") (pin "B21") (pinfunction "CLK0-_B21") (pintype "passive"))
    )
    (net (code "113") (name "/REFCLK0_P") (class "Default")
      (node (ref "U5") (pin "A21") (pinfunction "CLK0+_A21") (pintype "passive"))
    )
    (net (code "114") (name "/REFCLK1_N") (class "Default")
      (node (ref "U5") (pin "B20") (pinfunction "CLK1-_B20") (pintype "passive"))
    )
    (net (code "115") (name "/REFCLK1_P") (class "Default")
      (node (ref "U5") (pin "A20") (pinfunction "CLK1+_A20") (pintype "passive"))
    )
    (net (code "116") (name "/REFCLK2_N") (class "Default")
      (node (ref "U5") (pin "B19") (pinfunction "CLK2-_B19") (pintype "passive"))
    )
    (net (code "117") (name "/REFCLK2_P") (class "Default")
      (node (ref "U5") (pin "A19") (pinfunction "CLK2+_A19") (pintype "passive"))
    )
    (net (code "118") (name "/REFCLK3_N") (class "Default")
      (node (ref "U5") (pin "E17") (pinfunction "CLK3-_E17") (pintype "passive"))
    )
    (net (code "119") (name "/REFCLK3_P") (class "Default")
      (node (ref "U5") (pin "D17") (pinfunction "CLK3+_D17") (pintype "passive"))
    )
    (net (code "120") (name "/REFCLK4_N") (class "Default")
      (node (ref "U5") (pin "B18") (pinfunction "CLK4-_B18") (pintype "passive"))
    )
    (net (code "121") (name "/REFCLK4_P") (class "Default")
      (node (ref "U5") (pin "A18") (pinfunction "CLK4+_A18") (pintype "passive"))
    )
    (net (code "122") (name "/REFCLK5_N") (class "Default")
      (node (ref "U5") (pin "B17") (pinfunction "CLK5-_B17") (pintype "passive"))
    )
    (net (code "123") (name "/REFCLK5_P") (class "Default")
      (node (ref "U5") (pin "A17") (pinfunction "CLK5+_A17") (pintype "passive"))
    )
    (net (code "124") (name "/RST") (class "Default")
      (node (ref "U5") (pin "AC7") (pinfunction "RST_AC7") (pintype "passive"))
    )
    (net (code "125") (name "/SATA_SSC_EN") (class "Default")
      (node (ref "R20") (pin "2") (pinfunction "2_2") (pintype "passive"))
      (node (ref "R21") (pin "1") (pinfunction "1_1") (pintype "passive"))
      (node (ref "U5") (pin "B23") (pinfunction "GPIO_R4*_B23") (pintype "passive"))
    )
    (net (code "126") (name "/SPI_CS") (class "Default")
      (node (ref "U5") (pin "E1") (pinfunction "SPI_CS_E1") (pintype "passive"))
      (node (ref "U6") (pin "1") (pinfunction "CS#_1") (pintype "passive"))
    )
    (net (code "127") (name "/SPI_SCK-G2S0") (class "Default")
      (node (ref "R10") (pin "1") (pinfunction "1_1") (pintype "passive"))
      (node (ref "R9") (pin "2") (pinfunction "2_2") (pintype "passive"))
      (node (ref "U5") (pin "A1") (pinfunction "*SPI_SCL_A1") (pintype "passive"))
      (node (ref "U6") (pin "6") (pinfunction "SLCK_6") (pintype "passive"))
    )
    (net (code "128") (name "/SPI_SDI-G0S1") (class "Default")
      (node (ref "R14") (pin "2") (pinfunction "2_2") (pintype "passive"))
      (node (ref "R15") (pin "1") (pinfunction "1_1") (pintype "passive"))
      (node (ref "U5") (pin "A4") (pinfunction "*SPI_SDI_A4") (pintype "passive"))
      (node (ref "U6") (pin "2") (pinfunction "SO_2") (pintype "passive"))
    )
    (net (code "129") (name "/SPI_SDO-G0S2") (class "Default")
      (node (ref "R22") (pin "2") (pinfunction "2_2") (pintype "passive"))
      (node (ref "R23") (pin "1") (pinfunction "1_1") (pintype "passive"))
      (node (ref "U5") (pin "E2") (pinfunction "*SPI_SDO_E2") (pintype "passive"))
      (node (ref "U6") (pin "5") (pinfunction "SI_5") (pintype "passive"))
    )
    (net (code "130") (name "/SS0_RX_N") (class "Default")
      (node (ref "U5") (pin "Y12") (pinfunction "SS_RXN0_Y12") (pintype "passive"))
    )
    (net (code "131") (name "/SS0_RX_P") (class "Default")
      (node (ref "U5") (pin "W12") (pinfunction "SS_RXP0_W12") (pintype "passive"))
    )
    (net (code "132") (name "/SS0_TX_N") (class "Default")
      (node (ref "C53") (pin "1") (pinfunction "1_1") (pintype "passive"))
    )
    (net (code "133") (name "/SS0_TX_P") (class "Default")
      (node (ref "C52") (pin "1") (pinfunction "1_1") (pintype "passive"))
    )
    (net (code "134") (name "/SS1_RX_N") (class "Default")
      (node (ref "U5") (pin "W13") (pinfunction "SS_RXN1_W13") (pintype "passive"))
    )
    (net (code "135") (name "/SS1_RX_P") (class "Default")
      (node (ref "U5") (pin "Y13") (pinfunction "SS_RXP1_Y13") (pintype "passive"))
    )
    (net (code "136") (name "/SS1_TX_N") (class "Default")
      (node (ref "C58") (pin "1") (pinfunction "1_1") (pintype "passive"))
    )
    (net (code "137") (name "/SS1_TX_P") (class "Default")
      (node (ref "C56") (pin "1") (pinfunction "1_1") (pintype "passive"))
    )
    (net (code "138") (name "/SS2_RX_N") (class "Default")
      (node (ref "U5") (pin "Y15") (pinfunction "SS_RXN2_Y15") (pintype "passive"))
    )
    (net (code "139") (name "/SS2_RX_P") (class "Default")
      (node (ref "U5") (pin "W15") (pinfunction "SS_RXP2_W15") (pintype "passive"))
    )
    (net (code "140") (name "/SS2_TX_N") (class "Default")
      (node (ref "C63") (pin "1") (pinfunction "1_1") (pintype "passive"))
    )
    (net (code "141") (name "/SS2_TX_P") (class "Default")
      (node (ref "C61") (pin "1") (pinfunction "1_1") (pintype "passive"))
    )
    (net (code "142") (name "/SS3_RX_N") (class "Default")
      (node (ref "U5") (pin "Y16") (pinfunction "SS_RXN3_Y16") (pintype "passive"))
    )
    (net (code "143") (name "/SS3_RX_P") (class "Default")
      (node (ref "U5") (pin "W16") (pinfunction "SS_RXP3_W16") (pintype "passive"))
    )
    (net (code "144") (name "/SS3_TX_N") (class "Default")
      (node (ref "C67") (pin "1") (pinfunction "1_1") (pintype "passive"))
    )
    (net (code "145") (name "/SS3_TX_P") (class "Default")
      (node (ref "C66") (pin "1") (pinfunction "1_1") (pintype "passive"))
    )
    (net (code "146") (name "/SS4_RX_N") (class "Default")
      (node (ref "U5") (pin "Y18") (pinfunction "SS_RXN4_Y18") (pintype "passive"))
    )
    (net (code "147") (name "/SS4_RX_P") (class "Default")
      (node (ref "U5") (pin "W18") (pinfunction "SS_RXP4_W18") (pintype "passive"))
    )
    (net (code "148") (name "/SS4_TX_N") (class "Default")
      (node (ref "C72") (pin "1") (pinfunction "1_1") (pintype "passive"))
    )
    (net (code "149") (name "/SS4_TX_P") (class "Default")
      (node (ref "C70") (pin "1") (pinfunction "1_1") (pintype "passive"))
    )
    (net (code "150") (name "/SS5_RX_N") (class "Default")
      (node (ref "U5") (pin "Y19") (pinfunction "SS_RXN5_Y19") (pintype "passive"))
    )
    (net (code "151") (name "/SS5_RX_P") (class "Default")
      (node (ref "U5") (pin "W19") (pinfunction "SS_RXP5_W19") (pintype "passive"))
    )
    (net (code "152") (name "/SS5_TX_N") (class "Default")
      (node (ref "C77") (pin "1") (pinfunction "1_1") (pintype "passive"))
    )
    (net (code "153") (name "/SS5_TX_P") (class "Default")
      (node (ref "C75") (pin "1") (pinfunction "1_1") (pintype "passive"))
    )
    (net (code "154") (name "/STATUS0") (class "Default")
      (node (ref "R53") (pin "2") (pinfunction "2_2") (pintype "passive"))
      (node (ref "U5") (pin "AA10") (pinfunction "STATUS_IND_0_AA10") (pintype "passive"))
    )
    (net (code "155") (name "/STATUS1") (class "Default")
      (node (ref "R54") (pin "2") (pinfunction "2_2") (pintype "passive"))
      (node (ref "U5") (pin "Y10") (pinfunction "STATUS_IND2_0_Y10") (pintype "passive"))
    )
    (net (code "156") (name "/UPE_REFCLK_N") (class "Default")
      (node (ref "U5") (pin "E22") (pinfunction "UPE_CLK0-_E22") (pintype "passive"))
    )
    (net (code "157") (name "/UPE_REFCLK_P") (class "Default")
      (node (ref "U5") (pin "E23") (pinfunction "UPE_CLK+_E23") (pintype "passive"))
    )
    (net (code "158") (name "/UPE_RX0_N") (class "Default")
      (node (ref "U5") (pin "G5") (pinfunction "UPE_RX0-_G5") (pintype "passive"))
    )
    (net (code "159") (name "/UPE_RX0_P") (class "Default")
      (node (ref "U5") (pin "G4") (pinfunction "UPE_RX0+_G4") (pintype "passive"))
    )
    (net (code "160") (name "/UPE_RX1_N") (class "Default")
      (node (ref "U5") (pin "J5") (pinfunction "UPE_RX1-_J5") (pintype "passive"))
    )
    (net (code "161") (name "/UPE_RX1_P") (class "Default")
      (node (ref "U5") (pin "J4") (pinfunction "UPE_RX1+_J4") (pintype "passive"))
    )
    (net (code "162") (name "/UPE_RX2_N") (class "Default")
      (node (ref "U5") (pin "L5") (pinfunction "UPE_RX2-_L5") (pintype "passive"))
    )
    (net (code "163") (name "/UPE_RX2_P") (class "Default")
      (node (ref "U5") (pin "L4") (pinfunction "UPE_RX2+_L4") (pintype "passive"))
    )
    (net (code "164") (name "/UPE_RX3_N") (class "Default")
      (node (ref "U5") (pin "N5") (pinfunction "UPE_RX3-_N5") (pintype "passive"))
    )
    (net (code "165") (name "/UPE_RX3_P") (class "Default")
      (node (ref "U5") (pin "N4") (pinfunction "UPE_RX3+_N4") (pintype "passive"))
    )
    (net (code "166") (name "/UPE_TX0_N") (class "Default")
      (node (ref "C11") (pin "1") (pinfunction "1_1") (pintype "passive"))
    )
    (net (code "167") (name "/UPE_TX0_P") (class "Default")
      (node (ref "C10") (pin "1") (pinfunction "1_1") (pintype "passive"))
    )
    (net (code "168") (name "/UPE_TX1_N") (class "Default")
      (node (ref "C13") (pin "1") (pinfunction "1_1") (pintype "passive"))
    )
    (net (code "169") (name "/UPE_TX1_P") (class "Default")
      (node (ref "C12") (pin "1") (pinfunction "1_1") (pintype "passive"))
    )
    (net (code "170") (name "/UPE_TX2_N") (class "Default")
      (node (ref "C15") (pin "1") (pinfunction "1_1") (pintype "passive"))
    )
    (net (code "171") (name "/UPE_TX2_P") (class "Default")
      (node (ref "C14") (pin "1") (pinfunction "1_1") (pintype "passive"))
    )
    (net (code "172") (name "/UPE_TX3_N") (class "Default")
      (node (ref "C25") (pin "1") (pinfunction "1_1") (pintype "passive"))
    )
    (net (code "173") (name "/UPE_TX3_P") (class "Default")
      (node (ref "C16") (pin "1") (pinfunction "1_1") (pintype "passive"))
    )
    (net (code "174") (name "/UREXT") (class "Default")
      (node (ref "R51") (pin "2") (pinfunction "2_2") (pintype "passive"))
      (node (ref "U5") (pin "U23") (pinfunction "UREXT_U23") (pintype "passive"))
    )
    (net (code "175") (name "/USB0_D_N") (class "Default")
      (node (ref "U5") (pin "U2") (pinfunction "HSDN0_U2") (pintype "passive"))
    )
    (net (code "176") (name "/USB0_D_P") (class "Default")
      (node (ref "U5") (pin "U1") (pinfunction "HSDP0_U1") (pintype "passive"))
    )
    (net (code "177") (name "/USB1_D_N") (class "Default")
      (node (ref "U5") (pin "U4") (pinfunction "HSDN1_U4") (pintype "passive"))
    )
    (net (code "178") (name "/USB1_D_P") (class "Default")
      (node (ref "U5") (pin "U5") (pinfunction "HSDP1_U5") (pintype "passive"))
    )
    (net (code "179") (name "/USB2_D_N") (class "Default")
      (node (ref "U5") (pin "W1") (pinfunction "HSDN2_W1") (pintype "passive"))
    )
    (net (code "180") (name "/USB2_D_P") (class "Default")
      (node (ref "U5") (pin "V2") (pinfunction "HSDP2_V2") (pintype "passive"))
    )
    (net (code "181") (name "/USB3_D_N") (class "Default")
      (node (ref "U5") (pin "V4") (pinfunction "HSDN3_V4") (pintype "passive"))
    )
    (net (code "182") (name "/USB3_D_P") (class "Default")
      (node (ref "U5") (pin "V3") (pinfunction "HSDP3_V3") (pintype "passive"))
    )
    (net (code "183") (name "/USB4_D_N") (class "Default")
      (node (ref "U5") (pin "W2") (pinfunction "HSDN4_W2") (pintype "passive"))
    )
    (net (code "184") (name "/USB4_D_P") (class "Default")
      (node (ref "U5") (pin "Y1") (pinfunction "HSDP4_Y1") (pintype "passive"))
    )
    (net (code "185") (name "/USB5_D_N") (class "Default")
      (node (ref "U5") (pin "AA1") (pinfunction "HSDN5_AA1") (pintype "passive"))
    )
    (net (code "186") (name "/USB5_D_P") (class "Default")
      (node (ref "U5") (pin "AA2") (pinfunction "HSDP5_AA2") (pintype "passive"))
    )
    (net (code "187") (name "/USB6_D_N") (class "Default")
      (node (ref "U5") (pin "W3") (pinfunction "HSDN6_W3") (pintype "passive"))
    )
    (net (code "188") (name "/USB6_D_P") (class "Default")
      (node (ref "U5") (pin "Y3") (pinfunction "HSDP6_Y3") (pintype "passive"))
    )
    (net (code "189") (name "/USB7_D_N") (class "Default")
      (node (ref "U5") (pin "AB2") (pinfunction "HSDN7_AB2") (pintype "passive"))
    )
    (net (code "190") (name "/USB7_D_P") (class "Default")
      (node (ref "U5") (pin "AB1") (pinfunction "HSDP7_AB1") (pintype "passive"))
    )
    (net (code "191") (name "/USB8_D_N") (class "Default")
      (node (ref "U5") (pin "Y5") (pinfunction "HSDN8_Y5") (pintype "passive"))
    )
    (net (code "192") (name "/USB8_D_P") (class "Default")
      (node (ref "U5") (pin "Y4") (pinfunction "HSDP8_Y4") (pintype "passive"))
    )
    (net (code "193") (name "/USB9_D_N") (class "Default")
      (node (ref "U5") (pin "AA3") (pinfunction "HSDN9_AA3") (pintype "passive"))
    )
    (net (code "194") (name "/USB9_D_P") (class "Default")
      (node (ref "U5") (pin "AA4") (pinfunction "HSDP9_AA4") (pintype "passive"))
    )
    (net (code "195") (name "/USB10_D_N") (class "Default")
      (node (ref "U5") (pin "AC2") (pinfunction "HSDN10_AC2") (pintype "passive"))
    )
    (net (code "196") (name "/USB10_D_P") (class "Default")
      (node (ref "U5") (pin "AC3") (pinfunction "HSDP10_AC3") (pintype "passive"))
    )
    (net (code "197") (name "/USB11_D_N") (class "Default")
      (node (ref "U5") (pin "AC4") (pinfunction "HSDN11_AC4") (pintype "passive"))
    )
    (net (code "198") (name "/USB11_D_P") (class "Default")
      (node (ref "U5") (pin "AB4") (pinfunction "HSDP11_AB4") (pintype "passive"))
    )
    (net (code "199") (name "/USB_OC0") (class "Default")
      (node (ref "R42") (pin "2") (pinfunction "2_2") (pintype "passive"))
      (node (ref "U5") (pin "AC9") (pinfunction "USB_OC0_AC9") (pintype "passive"))
    )
    (net (code "200") (name "/USB_OC1") (class "Default")
      (node (ref "R43") (pin "2") (pinfunction "2_2") (pintype "passive"))
      (node (ref "U5") (pin "W7") (pinfunction "USB_OC1_W7") (pintype "passive"))
    )
    (net (code "201") (name "/USB_OC2") (class "Default")
      (node (ref "R44") (pin "2") (pinfunction "2_2") (pintype "passive"))
      (node (ref "U5") (pin "Y6") (pinfunction "USB_OC2_Y6") (pintype "passive"))
    )
    (net (code "202") (name "/USB_OC3") (class "Default")
      (node (ref "R46") (pin "2") (pinfunction "2_2") (pintype "passive"))
      (node (ref "U5") (pin "AC8") (pinfunction "USB_OC3_AC8") (pintype "passive"))
    )
    (net (code "203") (name "/USB_OC4") (class "Default")
      (node (ref "R47") (pin "2") (pinfunction "2_2") (pintype "passive"))
      (node (ref "U5") (pin "Y9") (pinfunction "USB_OC4_Y9") (pintype "passive"))
    )
    (net (code "204") (name "/USB_OC5") (class "Default")
      (node (ref "R48") (pin "2") (pinfunction "2_2") (pintype "passive"))
      (node (ref "U5") (pin "AA8") (pinfunction "USB_OC5_AA8") (pintype "passive"))
    )
    (net (code "205") (name "/USB_OC6") (class "Default")
      (node (ref "R49") (pin "2") (pinfunction "2_2") (pintype "passive"))
      (node (ref "U5") (pin "AA7") (pinfunction "USB_OC6_AA7") (pintype "passive"))
    )
    (net (code "206") (name "/USB_OC7") (class "Default")
      (node (ref "R50") (pin "2") (pinfunction "2_2") (pintype "passive"))
      (node (ref "U5") (pin "AA9") (pinfunction "USB_OC7_AA9") (pintype "passive"))
    )
    (net (code "207") (name "/USB_SSC_EN") (class "Default")
      (node (ref "R12") (pin "2") (pinfunction "2_2") (pintype "passive"))
      (node (ref "R13") (pin "1") (pinfunction "1_1") (pintype "passive"))
      (node (ref "U5") (pin "D20") (pinfunction "GPIO_R3*_D20") (pintype "passive"))
    )
    (net (code "208") (name "/WAKE#") (class "Default")
      (node (ref "U5") (pin "AC6") (pinfunction "PEWAKE_AC6") (pintype "passive"))
    )
    (net (code "209") (name "GND") (class "Default")
      (node (ref "C1") (pin "2") (pinfunction "2_2") (pintype "passive"))
      (node (ref "C17") (pin "2") (pinfunction "2_2") (pintype "passive"))
      (node (ref "C18") (pin "2") (pinfunction "2_2") (pintype "passive"))
      (node (ref "C19") (pin "2") (pinfunction "2_2") (pintype "passive"))
      (node (ref "C2") (pin "2") (pinfunction "2_2") (pintype "passive"))
      (node (ref "C20") (pin "2") (pinfunction "2_2") (pintype "passive"))
      (node (ref "C21") (pin "1") (pinfunction "1_1") (pintype "passive"))
      (node (ref "C22") (pin "2") (pinfunction "2_2") (pintype "passive"))
      (node (ref "C23") (pin "2") (pinfunction "2_2") (pintype "passive"))
      (node (ref "C24") (pin "2") (pinfunction "2_2") (pintype "passive"))
      (node (ref "C26") (pin "1") (pinfunction "1_1") (pintype "passive"))
      (node (ref "C27") (pin "2") (pinfunction "2_2") (pintype "passive"))
      (node (ref "C28") (pin "1") (pinfunction "1_1") (pintype "passive"))
      (node (ref "C29") (pin "2") (pinfunction "2_2") (pintype "passive"))
      (node (ref "C3") (pin "2") (pinfunction "2_2") (pintype "passive"))
      (node (ref "C30") (pin "2") (pinfunction "2_2") (pintype "passive"))
      (node (ref "C31") (pin "2") (pinfunction "2_2") (pintype "passive"))
      (node (ref "C32") (pin "2") (pinfunction "2_2") (pintype "passive"))
      (node (ref "C33") (pin "2") (pinfunction "2_2") (pintype "passive"))
      (node (ref "C34") (pin "1") (pinfunction "1_1") (pintype "passive"))
      (node (ref "C35") (pin "1") (pinfunction "1_1") (pintype "passive"))
      (node (ref "C36") (pin "1") (pinfunction "1_1") (pintype "passive"))
      (node (ref "C37") (pin "1") (pinfunction "1_1") (pintype "passive"))
      (node (ref "C38") (pin "1") (pinfunction "1_1") (pintype "passive"))
      (node (ref "C39") (pin "2") (pinfunction "2_2") (pintype "passive"))
      (node (ref "C4") (pin "2") (pinfunction "2_2") (pintype "passive"))
      (node (ref "C40") (pin "2") (pinfunction "2_2") (pintype "passive"))
      (node (ref "C41") (pin "2") (pinfunction "2_2") (pintype "passive"))
      (node (ref "C42") (pin "2") (pinfunction "2_2") (pintype "passive"))
      (node (ref "C43") (pin "1") (pinfunction "1_1") (pintype "passive"))
      (node (ref "C5") (pin "2") (pinfunction "2_2") (pintype "passive"))
      (node (ref "C6") (pin "2") (pinfunction "2_2") (pintype "passive"))
      (node (ref "C7") (pin "2") (pinfunction "2_2") (pintype "passive"))
      (node (ref "C8") (pin "2") (pinfunction "2_2") (pintype "passive"))
      (node (ref "C9") (pin "2") (pinfunction "2_2") (pintype "passive"))
      (node (ref "R12") (pin "1") (pinfunction "1_1") (pintype "passive"))
      (node (ref "R14") (pin "1") (pinfunction "1_1") (pintype "passive"))
      (node (ref "R16") (pin "1") (pinfunction "1_1") (pintype "passive"))
      (node (ref "R18") (pin "1") (pinfunction "1_1") (pintype "passive"))
      (node (ref "R20") (pin "1") (pinfunction "1_1") (pintype "passive"))
      (node (ref "R22") (pin "1") (pinfunction "1_1") (pintype "passive"))
      (node (ref "R24") (pin "1") (pinfunction "1_1") (pintype "passive"))
      (node (ref "R26") (pin "1") (pinfunction "1_1") (pintype "passive"))
      (node (ref "R28") (pin "1") (pinfunction "1_1") (pintype "passive"))
      (node (ref "R3") (pin "1") (pinfunction "1_1") (pintype "passive"))
      (node (ref "R32") (pin "2") (pinfunction "2_2") (pintype "passive"))
      (node (ref "R33") (pin "1") (pinfunction "1_1") (pintype "passive"))
      (node (ref "R35") (pin "1") (pinfunction "1_1") (pintype "passive"))
      (node (ref "R37") (pin "1") (pinfunction "1_1") (pintype "passive"))
      (node (ref "R39") (pin "2") (pinfunction "2_2") (pintype "passive"))
      (node (ref "R40") (pin "2") (pinfunction "2_2") (pintype "passive"))
      (node (ref "R41") (pin "2") (pinfunction "2_2") (pintype "passive"))
      (node (ref "R45") (pin "2") (pinfunction "2_2") (pintype "passive"))
      (node (ref "R5") (pin "1") (pinfunction "1_1") (pintype "passive"))
      (node (ref "R51") (pin "1") (pinfunction "1_1") (pintype "passive"))
      (node (ref "R56") (pin "1") (pinfunction "1_1") (pintype "passive"))
      (node (ref "R7") (pin "1") (pinfunction "1_1") (pintype "passive"))
      (node (ref "R9") (pin "1") (pinfunction "1_1") (pintype "passive"))
      (node (ref "U5") (pin "A10") (pinfunction "GNDA_A10") (pintype "passive"))
      (node (ref "U5") (pin "A13") (pinfunction "GNDA_A13") (pintype "passive"))
      (node (ref "U5") (pin "A16") (pinfunction "GNDA_A16") (pintype "passive"))
      (node (ref "U5") (pin "A7") (pinfunction "GNDA_A7") (pintype "passive"))
      (node (ref "U5") (pin "AA11") (pinfunction "GND1_AA11") (pintype "passive"))
      (node (ref "U5") (pin "AA12") (pinfunction "GND2_AA12") (pintype "passive"))
      (node (ref "U5") (pin "AA13") (pinfunction "GND3_AA13") (pintype "passive"))
      (node (ref "U5") (pin "AA14") (pinfunction "GND4_AA14") (pintype "passive"))
      (node (ref "U5") (pin "AA15") (pinfunction "GND5_AA15") (pintype "passive"))
      (node (ref "U5") (pin "AA16") (pinfunction "GND6_AA16") (pintype "passive"))
      (node (ref "U5") (pin "AA17") (pinfunction "GND7_AA17") (pintype "passive"))
      (node (ref "U5") (pin "AA18") (pinfunction "GND8_AA18") (pintype "passive"))
      (node (ref "U5") (pin "AA19") (pinfunction "GND9_AA19") (pintype "passive"))
      (node (ref "U5") (pin "AA20") (pinfunction "GNDA_AA20") (pintype "passive"))
      (node (ref "U5") (pin "AB11") (pinfunction "GNDA_AB11") (pintype "passive"))
      (node (ref "U5") (pin "AB14") (pinfunction "GNDA_AB14") (pintype "passive"))
      (node (ref "U5") (pin "AB17") (pinfunction "GNDA_AB17") (pintype "passive"))
      (node (ref "U5") (pin "AB20") (pinfunction "GNDA_AB20") (pintype "passive"))
      (node (ref "U5") (pin "AB3") (pinfunction "GNDA_AB3") (pintype "passive"))
      (node (ref "U5") (pin "AC1") (pinfunction "GNDA_AC1") (pintype "passive"))
      (node (ref "U5") (pin "AC11") (pinfunction "GNDA_AC11") (pintype "passive"))
      (node (ref "U5") (pin "AC14") (pinfunction "GNDA_AC14") (pintype "passive"))
      (node (ref "U5") (pin "AC17") (pinfunction "GNDA_AC17") (pintype "passive"))
      (node (ref "U5") (pin "AC20") (pinfunction "GNDA_AC20") (pintype "passive"))
      (node (ref "U5") (pin "B10") (pinfunction "GNDA_B10") (pintype "passive"))
      (node (ref "U5") (pin "B13") (pinfunction "GNDA_B13") (pintype "passive"))
      (node (ref "U5") (pin "B16") (pinfunction "GNDA_B16") (pintype "passive"))
      (node (ref "U5") (pin "B7") (pinfunction "GNDA_B7") (pintype "passive"))
      (node (ref "U5") (pin "C10") (pinfunction "GNDA_C10") (pintype "passive"))
      (node (ref "U5") (pin "C11") (pinfunction "GNDA_C11") (pintype "passive"))
      (node (ref "U5") (pin "C12") (pinfunction "GNDA_C12") (pintype "passive"))
      (node (ref "U5") (pin "C13") (pinfunction "GNDA_C13") (pintype "passive"))
      (node (ref "U5") (pin "C14") (pinfunction "GNDA_C14") (pintype "passive"))
      (node (ref "U5") (pin "C15") (pinfunction "GNDA_C15") (pintype "passive"))
      (node (ref "U5") (pin "C16") (pinfunction "GNDA_C16") (pintype "passive"))
      (node (ref "U5") (pin "C17") (pinfunction "GNDA_C17") (pintype "passive"))
      (node (ref "U5") (pin "C18") (pinfunction "GNDA_C18") (pintype "passive"))
      (node (ref "U5") (pin "C20") (pinfunction "GNDA_C20") (pintype "passive"))
      (node (ref "U5") (pin "C21") (pinfunction "GNDA_C21") (pintype "passive"))
      (node (ref "U5") (pin "C8") (pinfunction "GNDA_C8") (pintype "passive"))
      (node (ref "U5") (pin "C9") (pinfunction "GNDA_C9") (pintype "passive"))
      (node (ref "U5") (pin "D10") (pinfunction "GNDA_D10") (pintype "passive"))
      (node (ref "U5") (pin "D13") (pinfunction "GNDA_D13") (pintype "passive"))
      (node (ref "U5") (pin "D16") (pinfunction "GNDA_D16") (pintype "passive"))
      (node (ref "U5") (pin "E10") (pinfunction "GNDA_E10") (pintype "passive"))
      (node (ref "U5") (pin "E13") (pinfunction "GNDA_E13") (pintype "passive"))
      (node (ref "U5") (pin "E16") (pinfunction "GNDA_E16") (pintype "passive"))
      (node (ref "U5") (pin "E7") (pinfunction "GNDA_E7") (pintype "passive"))
      (node (ref "U5") (pin "F1") (pinfunction "GNDA_F1") (pintype "passive"))
      (node (ref "U5") (pin "F11") (pinfunction "GNDA_F11") (pintype "passive"))
      (node (ref "U5") (pin "F12") (pinfunction "GNDA_F12") (pintype "passive"))
      (node (ref "U5") (pin "F13") (pinfunction "GNDA_F13") (pintype "passive"))
      (node (ref "U5") (pin "F14") (pinfunction "GNDA_F14") (pintype "passive"))
      (node (ref "U5") (pin "F15") (pinfunction "GNDA_F15") (pintype "passive"))
      (node (ref "U5") (pin "F19") (pinfunction "GNDA_F19") (pintype "passive"))
      (node (ref "U5") (pin "F2") (pinfunction "GNDA_F2") (pintype "passive"))
      (node (ref "U5") (pin "F20") (pinfunction "GNDA_F20") (pintype "passive"))
      (node (ref "U5") (pin "F21") (pinfunction "GNDA_F21") (pintype "passive"))
      (node (ref "U5") (pin "F22") (pinfunction "GNDA_F22") (pintype "passive"))
      (node (ref "U5") (pin "F23") (pinfunction "GNDA_F23") (pintype "passive"))
      (node (ref "U5") (pin "F3") (pinfunction "GNDA_F3") (pintype "passive"))
      (node (ref "U5") (pin "F4") (pinfunction "GNDA_F4") (pintype "passive"))
      (node (ref "U5") (pin "F5") (pinfunction "GNDA_F5") (pintype "passive"))
      (node (ref "U5") (pin "F8") (pinfunction "GNDA_F8") (pintype "passive"))
      (node (ref "U5") (pin "F9") (pinfunction "GNDA_F9") (pintype "passive"))
      (node (ref "U5") (pin "G18") (pinfunction "GNDA_G18") (pintype "passive"))
      (node (ref "U5") (pin "G21") (pinfunction "GNDA_G21") (pintype "passive"))
      (node (ref "U5") (pin "G3") (pinfunction "GNDA_G3") (pintype "passive"))
      (node (ref "U5") (pin "G6") (pinfunction "GNDA_G6") (pintype "passive"))
      (node (ref "U5") (pin "H1") (pinfunction "GNDA_H1") (pintype "passive"))
      (node (ref "U5") (pin "H18") (pinfunction "GNDA_H18") (pintype "passive"))
      (node (ref "U5") (pin "H2") (pinfunction "GNDA_H2") (pintype "passive"))
      (node (ref "U5") (pin "H21") (pinfunction "GNDA_H21") (pintype "passive"))
      (node (ref "U5") (pin "H3") (pinfunction "GNDA_H3") (pintype "passive"))
      (node (ref "U5") (pin "H4") (pinfunction "GNDA_H4") (pintype "passive"))
      (node (ref "U5") (pin "H5") (pinfunction "GNDA_H5") (pintype "passive"))
      (node (ref "U5") (pin "H6") (pinfunction "GNDA_H6") (pintype "passive"))
      (node (ref "U5") (pin "J18") (pinfunction "GNDA_J18") (pintype "passive"))
      (node (ref "U5") (pin "J19") (pinfunction "GNDA_J19") (pintype "passive"))
      (node (ref "U5") (pin "J20") (pinfunction "GNDA_J20") (pintype "passive"))
      (node (ref "U5") (pin "J21") (pinfunction "GNDA_J21") (pintype "passive"))
      (node (ref "U5") (pin "J22") (pinfunction "GNDA_J22") (pintype "passive"))
      (node (ref "U5") (pin "J23") (pinfunction "GNDA_J23") (pintype "passive"))
      (node (ref "U5") (pin "J3") (pinfunction "GNDA_J3") (pintype "passive"))
      (node (ref "U5") (pin "J6") (pinfunction "GNDA_J6") (pintype "passive"))
      (node (ref "U5") (pin "K1") (pinfunction "GNDA_K1") (pintype "passive"))
      (node (ref "U5") (pin "K12") (pinfunction "GNDA_K12") (pintype "passive"))
      (node (ref "U5") (pin "K18") (pinfunction "GNDA_K18") (pintype "passive"))
      (node (ref "U5") (pin "K2") (pinfunction "GNDA_K2") (pintype "passive"))
      (node (ref "U5") (pin "K21") (pinfunction "GNDA_K21") (pintype "passive"))
      (node (ref "U5") (pin "K3") (pinfunction "GNDA_K3") (pintype "passive"))
      (node (ref "U5") (pin "K4") (pinfunction "GNDA_K4") (pintype "passive"))
      (node (ref "U5") (pin "K5") (pinfunction "GNDA_K5") (pintype "passive"))
      (node (ref "U5") (pin "K6") (pinfunction "GNDA_K6") (pintype "passive"))
      (node (ref "U5") (pin "L11") (pinfunction "GNDA_L11") (pintype "passive"))
      (node (ref "U5") (pin "L13") (pinfunction "GNDA_L13") (pintype "passive"))
      (node (ref "U5") (pin "L18") (pinfunction "GNDA_L18") (pintype "passive"))
      (node (ref "U5") (pin "L21") (pinfunction "GNDA_L21") (pintype "passive"))
      (node (ref "U5") (pin "L3") (pinfunction "GNDA_L3") (pintype "passive"))
      (node (ref "U5") (pin "L6") (pinfunction "GNDA_L6") (pintype "passive"))
      (node (ref "U5") (pin "M1") (pinfunction "GNDA_M1") (pintype "passive"))
      (node (ref "U5") (pin "M10") (pinfunction "GNDA_M10") (pintype "passive"))
      (node (ref "U5") (pin "M12") (pinfunction "GNDA_M12") (pintype "passive"))
      (node (ref "U5") (pin "M14") (pinfunction "GNDA_M14") (pintype "passive"))
      (node (ref "U5") (pin "M18") (pinfunction "GNDA_M18") (pintype "passive"))
      (node (ref "U5") (pin "M19") (pinfunction "GNDA_M19") (pintype "passive"))
      (node (ref "U5") (pin "M2") (pinfunction "GNDA_M2") (pintype "passive"))
      (node (ref "U5") (pin "M20") (pinfunction "GNDA_M20") (pintype "passive"))
      (node (ref "U5") (pin "M21") (pinfunction "GNDA_M21") (pintype "passive"))
      (node (ref "U5") (pin "M22") (pinfunction "GNDA_M22") (pintype "passive"))
      (node (ref "U5") (pin "M23") (pinfunction "GNDA_M23") (pintype "passive"))
      (node (ref "U5") (pin "M3") (pinfunction "GNDA_M3") (pintype "passive"))
      (node (ref "U5") (pin "M4") (pinfunction "GNDA_M4") (pintype "passive"))
      (node (ref "U5") (pin "M5") (pinfunction "GNDA_M5") (pintype "passive"))
      (node (ref "U5") (pin "M6") (pinfunction "GNDA_M6") (pintype "passive"))
      (node (ref "U5") (pin "N11") (pinfunction "GND_N11") (pintype "passive"))
      (node (ref "U5") (pin "N13") (pinfunction "GND_N13") (pintype "passive"))
      (node (ref "U5") (pin "N18") (pinfunction "GNDA_N18") (pintype "passive"))
      (node (ref "U5") (pin "N21") (pinfunction "GNDA_N21") (pintype "passive"))
      (node (ref "U5") (pin "N3") (pinfunction "GNDA_N3") (pintype "passive"))
      (node (ref "U5") (pin "N6") (pinfunction "GNDA_N6") (pintype "passive"))
      (node (ref "U5") (pin "P1") (pinfunction "GNDA_P1") (pintype "passive"))
      (node (ref "U5") (pin "P12") (pinfunction "GND_P12") (pintype "passive"))
      (node (ref "U5") (pin "P18") (pinfunction "GNDA_P18") (pintype "passive"))
      (node (ref "U5") (pin "P2") (pinfunction "GNDA_P2") (pintype "passive"))
      (node (ref "U5") (pin "P21") (pinfunction "GNDA_P21") (pintype "passive"))
      (node (ref "U5") (pin "P3") (pinfunction "GNDA_P3") (pintype "passive"))
      (node (ref "U5") (pin "P4") (pinfunction "GNDA_P4") (pintype "passive"))
      (node (ref "U5") (pin "P5") (pinfunction "GNDA_P5") (pintype "passive"))
      (node (ref "U5") (pin "P6") (pinfunction "GNDA_P6") (pintype "passive"))
      (node (ref "U5") (pin "R19") (pinfunction "GNDA_R19") (pintype "passive"))
      (node (ref "U5") (pin "R20") (pinfunction "GNDA_R20") (pintype "passive"))
      (node (ref "U5") (pin "R21") (pinfunction "GNDA_R21") (pintype "passive"))
      (node (ref "U5") (pin "R22") (pinfunction "GNDA_R22") (pintype "passive"))
      (node (ref "U5") (pin "R23") (pinfunction "GNDA_R23") (pintype "passive"))
      (node (ref "U5") (pin "T20") (pinfunction "*TSETN_T20") (pintype "passive"))
      (node (ref "U5") (pin "T21") (pinfunction "GNDA_T21") (pintype "passive"))
      (node (ref "U5") (pin "U21") (pinfunction "*DBG_ENABLE_U21") (pintype "passive"))
      (node (ref "U5") (pin "U3") (pinfunction "GNDA_U3") (pintype "passive"))
      (node (ref "U5") (pin "V1") (pinfunction "GNDA_V1") (pintype "passive"))
      (node (ref "U5") (pin "V11") (pinfunction "GNDA_V11") (pintype "passive"))
      (node (ref "U5") (pin "V12") (pinfunction "GNDA_V12") (pintype "passive"))
      (node (ref "U5") (pin "V13") (pinfunction "GNDA_V13") (pintype "passive"))
      (node (ref "U5") (pin "V14") (pinfunction "GNDA_V14") (pintype "passive"))
      (node (ref "U5") (pin "V15") (pinfunction "GNDA_V15") (pintype "passive"))
      (node (ref "U5") (pin "V16") (pinfunction "GNDA_V16") (pintype "passive"))
      (node (ref "U5") (pin "V17") (pinfunction "GNDA_V17") (pintype "passive"))
      (node (ref "U5") (pin "V18") (pinfunction "GNDA_V18") (pintype "passive"))
      (node (ref "U5") (pin "V19") (pinfunction "GNDA_V19") (pintype "passive"))
      (node (ref "U5") (pin "V5") (pinfunction "GNDA_V5") (pintype "passive"))
      (node (ref "U5") (pin "W11") (pinfunction "GNDA_W11") (pintype "passive"))
      (node (ref "U5") (pin "W14") (pinfunction "GNDA_W14") (pintype "passive"))
      (node (ref "U5") (pin "W17") (pinfunction "GNDA_W17") (pintype "passive"))
      (node (ref "U5") (pin "W20") (pinfunction "GNDA_W20") (pintype "passive"))
      (node (ref "U5") (pin "W4") (pinfunction "GNDA_W4") (pintype "passive"))
      (node (ref "U5") (pin "W5") (pinfunction "GNDA_W5") (pintype "passive"))
      (node (ref "U5") (pin "Y11") (pinfunction "GNDA_Y11") (pintype "passive"))
      (node (ref "U5") (pin "Y14") (pinfunction "GNDA_Y14") (pintype "passive"))
      (node (ref "U5") (pin "Y17") (pinfunction "GNDA_Y17") (pintype "passive"))
      (node (ref "U5") (pin "Y2") (pinfunction "GNDA_Y2") (pintype "passive"))
      (node (ref "U5") (pin "Y20") (pinfunction "GNDA_Y20") (pintype "passive"))
      (node (ref "U6") (pin "4") (pinfunction "GND_4") (pintype "passive"))
      (node (ref "Y1") (pin "2") (pinfunction "GND_2") (pintype "passive"))
      (node (ref "Y1") (pin "4") (pinfunction "GND_4") (pintype "passive"))
    )
    (net (code "210") (name "Net-(U5A-CLKREQ#)") (class "Default")
      (node (ref "R39") (pin "1") (pinfunction "1_1") (pintype "passive"))
      (node (ref "U5") (pin "A23") (pinfunction "CLKREQ#_A23") (pintype "passive"))
    )
    (net (code "211") (name "Net-(U5A-PREXT)") (class "Default")
      (node (ref "R40") (pin "1") (pinfunction "1_1") (pintype "passive"))
      (node (ref "U5") (pin "D23") (pinfunction "PREXT_D23") (pintype "passive"))
    )
    (net (code "212") (name "Net-(U5B-IFDET0)") (class "Default")
      (node (ref "R41") (pin "1") (pinfunction "1_1") (pintype "passive"))
      (node (ref "U5") (pin "E3") (pinfunction "IFDET0_E3") (pintype "passive"))
    )
    (net (code "213") (name "Net-(U5B-IFDET1)") (class "Default")
      (node (ref "R45") (pin "1") (pinfunction "1_1") (pintype "passive"))
      (node (ref "U5") (pin "E4") (pinfunction "IFDET1_E4") (pintype "passive"))
    )
    (net (code "214") (name "Net-(U5C-PPON_11)") (class "Default")
      (node (ref "R52") (pin "1") (pinfunction "1_1") (pintype "passive"))
      (node (ref "R56") (pin "2") (pinfunction "2_2") (pintype "passive"))
      (node (ref "U5") (pin "AB5") (pinfunction "PPON_11_AB5") (pintype "passive"))
    )
    (net (code "215") (name "Net-(U5D-INT)") (class "Default")
      (node (ref "R11") (pin "1") (pinfunction "1_1") (pintype "passive"))
      (node (ref "U5") (pin "V23") (pinfunction "INT_V23") (pintype "passive"))
    )
    (net (code "216") (name "Net-(U5D-RTCK)") (class "Default")
      (node (ref "R32") (pin "1") (pinfunction "1_1") (pintype "passive"))
      (node (ref "U5") (pin "Y22") (pinfunction "RTCK_Y22") (pintype "passive"))
    )
    (net (code "217") (name "Net-(U6-HOLD#)") (class "Default")
      (node (ref "R31") (pin "1") (pinfunction "1_1") (pintype "passive"))
      (node (ref "U6") (pin "7") (pinfunction "HOLD#_7") (pintype "passive"))
    )
    (net (code "218") (name "Net-(U6-WP#)") (class "Default")
      (node (ref "R30") (pin "2") (pinfunction "2_2") (pintype "passive"))
      (node (ref "U6") (pin "3") (pinfunction "WP#_3") (pintype "passive"))
    )
    (net (code "219") (name "VCC1.05V") (class "Default")
      (node (ref "C2") (pin "1") (pinfunction "1_1") (pintype "passive"))
      (node (ref "C21") (pin "2") (pinfunction "2_2") (pintype "passive"))
      (node (ref "C22") (pin "1") (pinfunction "1_1") (pintype "passive"))
      (node (ref "C23") (pin "1") (pinfunction "1_1") (pintype "passive"))
      (node (ref "C24") (pin "1") (pinfunction "1_1") (pintype "passive"))
      (node (ref "C3") (pin "1") (pinfunction "1_1") (pintype "passive"))
      (node (ref "C4") (pin "1") (pinfunction "1_1") (pintype "passive"))
      (node (ref "C5") (pin "1") (pinfunction "1_1") (pintype "passive"))
      (node (ref "C6") (pin "1") (pinfunction "1_1") (pintype "passive"))
      (node (ref "C7") (pin "1") (pinfunction "1_1") (pintype "passive"))
      (node (ref "C8") (pin "1") (pinfunction "1_1") (pintype "passive"))
      (node (ref "C9") (pin "1") (pinfunction "1_1") (pintype "passive"))
      (node (ref "U5") (pin "J12") (pinfunction "VDD105_J12") (pintype "passive"))
      (node (ref "U5") (pin "K10") (pinfunction "VDD105_K10") (pintype "passive"))
      (node (ref "U5") (pin "K11") (pinfunction "VDD105_K11") (pintype "passive"))
      (node (ref "U5") (pin "K13") (pinfunction "VDD105_K13") (pintype "passive"))
      (node (ref "U5") (pin "K14") (pinfunction "VDD105_K14") (pintype "passive"))
      (node (ref "U5") (pin "L10") (pinfunction "VDD105_L10") (pintype "passive"))
      (node (ref "U5") (pin "L12") (pinfunction "VDD105_L12") (pintype "passive"))
      (node (ref "U5") (pin "L14") (pinfunction "VDD105_L14") (pintype "passive"))
      (node (ref "U5") (pin "M11") (pinfunction "VDD105_M11") (pintype "passive"))
      (node (ref "U5") (pin "M13") (pinfunction "VDD105_M13") (pintype "passive"))
      (node (ref "U5") (pin "N10") (pinfunction "VDD105_N10") (pintype "passive"))
      (node (ref "U5") (pin "N12") (pinfunction "VDD105_N12") (pintype "passive"))
      (node (ref "U5") (pin "N14") (pinfunction "VDD105_N14") (pintype "passive"))
      (node (ref "U5") (pin "N9") (pinfunction "VDD105_N9") (pintype "passive"))
      (node (ref "U5") (pin "P10") (pinfunction "VDD105_P10") (pintype "passive"))
      (node (ref "U5") (pin "P11") (pinfunction "VDD105_P11") (pintype "passive"))
      (node (ref "U5") (pin "P13") (pinfunction "VDD105_P13") (pintype "passive"))
      (node (ref "U5") (pin "P14") (pinfunction "VDD105_P14") (pintype "passive"))
      (node (ref "U5") (pin "P9") (pinfunction "VDD105_P9") (pintype "passive"))
      (node (ref "U5") (pin "R1") (pinfunction "VDD105_R1") (pintype "passive"))
      (node (ref "U5") (pin "R15") (pinfunction "VDD105_R15") (pintype "passive"))
      (node (ref "U5") (pin "R2") (pinfunction "VDD105_R2") (pintype "passive"))
      (node (ref "U5") (pin "R3") (pinfunction "VDD105_R3") (pintype "passive"))
      (node (ref "U5") (pin "R4") (pinfunction "VDD105_R4") (pintype "passive"))
      (node (ref "U5") (pin "R5") (pinfunction "VDD105_R5") (pintype "passive"))
      (node (ref "U5") (pin "R6") (pinfunction "VDD105_R6") (pintype "passive"))
      (node (ref "U5") (pin "T1") (pinfunction "VDD105_T1") (pintype "passive"))
      (node (ref "U5") (pin "T2") (pinfunction "VDD105_T2") (pintype "passive"))
      (node (ref "U5") (pin "T3") (pinfunction "VDD105_T3") (pintype "passive"))
      (node (ref "U5") (pin "T4") (pinfunction "VDD105_T4") (pintype "passive"))
      (node (ref "U5") (pin "T5") (pinfunction "VDD105_T5") (pintype "passive"))
      (node (ref "U5") (pin "T6") (pinfunction "VDD105_T6") (pintype "passive"))
    )
    (net (code "220") (name "VCC1.8V") (class "Default")
      (node (ref "C17") (pin "1") (pinfunction "1_1") (pintype "passive"))
      (node (ref "C18") (pin "1") (pinfunction "1_1") (pintype "passive"))
      (node (ref "C19") (pin "1") (pinfunction "1_1") (pintype "passive"))
      (node (ref "C20") (pin "1") (pinfunction "1_1") (pintype "passive"))
      (node (ref "C28") (pin "2") (pinfunction "2_2") (pintype "passive"))
      (node (ref "C29") (pin "1") (pinfunction "1_1") (pintype "passive"))
      (node (ref "C30") (pin "1") (pinfunction "1_1") (pintype "passive"))
      (node (ref "C31") (pin "1") (pinfunction "1_1") (pintype "passive"))
      (node (ref "C32") (pin "1") (pinfunction "1_1") (pintype "passive"))
      (node (ref "C33") (pin "1") (pinfunction "1_1") (pintype "passive"))
      (node (ref "U5") (pin "A5") (pinfunction "VCC18_A5") (pintype "passive"))
      (node (ref "U5") (pin "A6") (pinfunction "VCC18_A6") (pintype "passive"))
      (node (ref "U5") (pin "B5") (pinfunction "VCC18_B5") (pintype "passive"))
      (node (ref "U5") (pin "B6") (pinfunction "VCC18_B6") (pintype "passive"))
      (node (ref "U5") (pin "C6") (pinfunction "VCC18_C6") (pintype "passive"))
      (node (ref "U5") (pin "C7") (pinfunction "VCC18_C7") (pintype "passive"))
      (node (ref "U5") (pin "D6") (pinfunction "VCC18_D6") (pintype "passive"))
      (node (ref "U5") (pin "D7") (pinfunction "VCC18_D7") (pintype "passive"))
      (node (ref "U5") (pin "E6") (pinfunction "VCC18_E6") (pintype "passive"))
      (node (ref "U5") (pin "J10") (pinfunction "VCC18_J10") (pintype "passive"))
      (node (ref "U5") (pin "J11") (pinfunction "VCC18_J11") (pintype "passive"))
      (node (ref "U5") (pin "J13") (pinfunction "VCC18_J13") (pintype "passive"))
      (node (ref "U5") (pin "J14") (pinfunction "VCC18_J14") (pintype "passive"))
      (node (ref "U5") (pin "J15") (pinfunction "VCC18_J15") (pintype "passive"))
      (node (ref "U5") (pin "J9") (pinfunction "VCC18_J9") (pintype "passive"))
      (node (ref "U5") (pin "K15") (pinfunction "VCC18_K15") (pintype "passive"))
      (node (ref "U5") (pin "K9") (pinfunction "VCC18_K9") (pintype "passive"))
      (node (ref "U5") (pin "L15") (pinfunction "VCC18_L15") (pintype "passive"))
      (node (ref "U5") (pin "L9") (pinfunction "VCC18_L9") (pintype "passive"))
      (node (ref "U5") (pin "M15") (pinfunction "VCC18_M15") (pintype "passive"))
      (node (ref "U5") (pin "M9") (pinfunction "VCC18_M9") (pintype "passive"))
      (node (ref "U5") (pin "N15") (pinfunction "VCC18_N15") (pintype "passive"))
      (node (ref "U5") (pin "P15") (pinfunction "VCC18_P15") (pintype "passive"))
      (node (ref "U5") (pin "R10") (pinfunction "VCC18_R10") (pintype "passive"))
      (node (ref "U5") (pin "R11") (pinfunction "VCC18_R11") (pintype "passive"))
      (node (ref "U5") (pin "R12") (pinfunction "VCC18_R12") (pintype "passive"))
      (node (ref "U5") (pin "R13") (pinfunction "VCC18_R13") (pintype "passive"))
      (node (ref "U5") (pin "R14") (pinfunction "VCC18_R14") (pintype "passive"))
      (node (ref "U5") (pin "R9") (pinfunction "VCC18_R9") (pintype "passive"))
    )
    (net (code "221") (name "VSUS1.05V") (class "Default")
      (node (ref "C26") (pin "2") (pinfunction "2_2") (pintype "passive"))
      (node (ref "C27") (pin "1") (pinfunction "1_1") (pintype "passive"))
      (node (ref "U5") (pin "U6") (pinfunction "VSUS105_U6") (pintype "passive"))
    )
    (net (code "222") (name "VSUS3.3V") (class "Default")
      (node (ref "C1") (pin "1") (pinfunction "1_1") (pintype "passive"))
      (node (ref "C35") (pin "2") (pinfunction "2_2") (pintype "passive"))
      (node (ref "C36") (pin "2") (pinfunction "2_2") (pintype "passive"))
      (node (ref "C37") (pin "2") (pinfunction "2_2") (pintype "passive"))
      (node (ref "C38") (pin "2") (pinfunction "2_2") (pintype "passive"))
      (node (ref "C39") (pin "1") (pinfunction "1_1") (pintype "passive"))
      (node (ref "C40") (pin "1") (pinfunction "1_1") (pintype "passive"))
      (node (ref "C41") (pin "1") (pinfunction "1_1") (pintype "passive"))
      (node (ref "C42") (pin "1") (pinfunction "1_1") (pintype "passive"))
      (node (ref "R10") (pin "2") (pinfunction "2_2") (pintype "passive"))
      (node (ref "R11") (pin "2") (pinfunction "2_2") (pintype "passive"))
      (node (ref "R13") (pin "2") (pinfunction "2_2") (pintype "passive"))
      (node (ref "R15") (pin "2") (pinfunction "2_2") (pintype "passive"))
      (node (ref "R17") (pin "2") (pinfunction "2_2") (pintype "passive"))
      (node (ref "R19") (pin "2") (pinfunction "2_2") (pintype "passive"))
      (node (ref "R21") (pin "2") (pinfunction "2_2") (pintype "passive"))
      (node (ref "R23") (pin "2") (pinfunction "2_2") (pintype "passive"))
      (node (ref "R25") (pin "2") (pinfunction "2_2") (pintype "passive"))
      (node (ref "R27") (pin "2") (pinfunction "2_2") (pintype "passive"))
      (node (ref "R29") (pin "2") (pinfunction "2_2") (pintype "passive"))
      (node (ref "R30") (pin "1") (pinfunction "1_1") (pintype "passive"))
      (node (ref "R31") (pin "2") (pinfunction "2_2") (pintype "passive"))
      (node (ref "R34") (pin "1") (pinfunction "1_1") (pintype "passive"))
      (node (ref "R36") (pin "1") (pinfunction "1_1") (pintype "passive"))
      (node (ref "R38") (pin "1") (pinfunction "1_1") (pintype "passive"))
      (node (ref "R4") (pin "2") (pinfunction "2_2") (pintype "passive"))
      (node (ref "R42") (pin "1") (pinfunction "1_1") (pintype "passive"))
      (node (ref "R43") (pin "1") (pinfunction "1_1") (pintype "passive"))
      (node (ref "R44") (pin "1") (pinfunction "1_1") (pintype "passive"))
      (node (ref "R46") (pin "1") (pinfunction "1_1") (pintype "passive"))
      (node (ref "R47") (pin "1") (pinfunction "1_1") (pintype "passive"))
      (node (ref "R48") (pin "1") (pinfunction "1_1") (pintype "passive"))
      (node (ref "R49") (pin "1") (pinfunction "1_1") (pintype "passive"))
      (node (ref "R50") (pin "1") (pinfunction "1_1") (pintype "passive"))
      (node (ref "R52") (pin "2") (pinfunction "2_2") (pintype "passive"))
      (node (ref "R53") (pin "1") (pinfunction "1_1") (pintype "passive"))
      (node (ref "R54") (pin "1") (pinfunction "1_1") (pintype "passive"))
      (node (ref "R55") (pin "1") (pinfunction "1_1") (pintype "passive"))
      (node (ref "R6") (pin "2") (pinfunction "2_2") (pintype "passive"))
      (node (ref "R8") (pin "2") (pinfunction "2_2") (pintype "passive"))
      (node (ref "U5") (pin "F10") (pinfunction "VCC33_F10") (pintype "passive"))
      (node (ref "U5") (pin "F16") (pinfunction "VCC33_F16") (pintype "passive"))
      (node (ref "U5") (pin "P7") (pinfunction "VSUS33_P7") (pintype "passive"))
      (node (ref "U5") (pin "R18") (pinfunction "VCC33_R18") (pintype "passive"))
      (node (ref "U6") (pin "8") (pinfunction "VCC_8") (pintype "passive"))
    )
    (net (code "223") (name "unconnected-(U5A-SMI-PadD5)") (class "Default")
      (node (ref "U5") (pin "D5") (pinfunction "SMI_D5") (pintype "passive+no_connect"))
    )
    (net (code "224") (name "unconnected-(U5B-SATALED0-PadA3)") (class "Default")
      (node (ref "U5") (pin "A3") (pinfunction "SATALED0_A3") (pintype "passive+no_connect"))
    )
    (net (code "225") (name "unconnected-(U5B-SATALED1-PadC5)") (class "Default")
      (node (ref "U5") (pin "C5") (pinfunction "SATALED1_C5") (pintype "passive+no_connect"))
    )
    (net (code "226") (name "unconnected-(U5B-SATALED2-PadE5)") (class "Default")
      (node (ref "U5") (pin "E5") (pinfunction "SATALED2_E5") (pintype "passive+no_connect"))
    )
    (net (code "227") (name "unconnected-(U5B-SATALED3-PadD1)") (class "Default")
      (node (ref "U5") (pin "D1") (pinfunction "SATALED3_D1") (pintype "passive+no_connect"))
    )
    (net (code "228") (name "unconnected-(U5C-PPON_0-PadAC10)") (class "Default")
      (node (ref "U5") (pin "AC10") (pinfunction "PPON_0_AC10") (pintype "passive+no_connect"))
    )
    (net (code "229") (name "unconnected-(U5C-PPON_2-PadAB8)") (class "Default")
      (node (ref "U5") (pin "AB8") (pinfunction "PPON_2_AB8") (pintype "passive+no_connect"))
    )
    (net (code "230") (name "unconnected-(U5C-PPON_2-PadAB9)") (class "Default")
      (node (ref "U5") (pin "AB9") (pinfunction "PPON_2_AB9") (pintype "passive+no_connect"))
    )
    (net (code "231") (name "unconnected-(U5C-PPON_3-PadAB7)") (class "Default")
      (node (ref "U5") (pin "AB7") (pinfunction "PPON_3_AB7") (pintype "passive+no_connect"))
    )
    (net (code "232") (name "unconnected-(U5C-PPON_4-PadW8)") (class "Default")
      (node (ref "U5") (pin "W8") (pinfunction "PPON_4_W8") (pintype "passive+no_connect"))
    )
    (net (code "233") (name "unconnected-(U5C-PPON_5-PadAA6)") (class "Default")
      (node (ref "U5") (pin "AA6") (pinfunction "PPON_5_AA6") (pintype "passive+no_connect"))
    )
    (net (code "234") (name "unconnected-(U5C-PPON_6-PadW6)") (class "Default")
      (node (ref "U5") (pin "W6") (pinfunction "PPON_6_W6") (pintype "passive+no_connect"))
    )
    (net (code "235") (name "unconnected-(U5C-PPON_7-PadAA5)") (class "Default")
      (node (ref "U5") (pin "AA5") (pinfunction "PPON_7_AA5") (pintype "passive+no_connect"))
    )
    (net (code "236") (name "unconnected-(U5C-PPON_8-PadY8)") (class "Default")
      (node (ref "U5") (pin "Y8") (pinfunction "PPON_8_Y8") (pintype "passive+no_connect"))
    )
    (net (code "237") (name "unconnected-(U5C-PPON_9-PadAB6)") (class "Default")
      (node (ref "U5") (pin "AB6") (pinfunction "PPON_9_AB6") (pintype "passive+no_connect"))
    )
    (net (code "238") (name "unconnected-(U5C-PPON_10-PadY7)") (class "Default")
      (node (ref "U5") (pin "Y7") (pinfunction "PPON_10_Y7") (pintype "passive+no_connect"))
    )
    (net (code "239") (name "unconnected-(U5D-*TCK-PadW23)") (class "Default")
      (node (ref "U5") (pin "W23") (pinfunction "*TCK_W23") (pintype "passive+no_connect"))
    )
    (net (code "240") (name "unconnected-(U5D-*TDO-PadAA22)") (class "Default")
      (node (ref "U5") (pin "AA22") (pinfunction "*TDO_AA22") (pintype "passive+no_connect"))
    )
    (net (code "241") (name "unconnected-(U5D-EFUSE_PWR-PadU20)") (class "Default")
      (node (ref "U5") (pin "U20") (pinfunction "EFUSE_PWR_U20") (pintype "passive+no_connect"))
    )
    (net (code "242") (name "unconnected-(U5D-GPIO0-PadB3)") (class "Default")
      (node (ref "U5") (pin "B3") (pinfunction "GPIO0_B3") (pintype "passive+no_connect"))
    )
    (net (code "243") (name "unconnected-(U5D-GPIO1-PadC4)") (class "Default")
      (node (ref "U5") (pin "C4") (pinfunction "GPIO1_C4") (pintype "passive+no_connect"))
    )
    (net (code "244") (name "unconnected-(U5D-GPIO2-PadA2)") (class "Default")
      (node (ref "U5") (pin "A2") (pinfunction "GPIO2_A2") (pintype "passive+no_connect"))
    )
    (net (code "245") (name "unconnected-(U5D-GPIO3-PadD3)") (class "Default")
      (node (ref "U5") (pin "D3") (pinfunction "GPIO3_D3") (pintype "passive+no_connect"))
    )
    (net (code "246") (name "unconnected-(U5D-GPIO4-PadD2)") (class "Default")
      (node (ref "U5") (pin "D2") (pinfunction "GPIO4_D2") (pintype "passive+no_connect"))
    )
    (net (code "247") (name "unconnected-(U5D-GPIO5-PadB4)") (class "Default")
      (node (ref "U5") (pin "B4") (pinfunction "GPIO5_B4") (pintype "passive+no_connect"))
    )
    (net (code "248") (name "unconnected-(U5D-GPIO6-PadC3)") (class "Default")
      (node (ref "U5") (pin "C3") (pinfunction "GPIO6_C3") (pintype "passive+no_connect"))
    )
    (net (code "249") (name "unconnected-(U5D-GPIO7-PadD4)") (class "Default")
      (node (ref "U5") (pin "D4") (pinfunction "GPIO7_D4") (pintype "passive+no_connect"))
    )
    (net (code "250") (name "unconnected-(U5D-GPIO8-PadD22)") (class "Default")
      (node (ref "U5") (pin "D22") (pinfunction "GPIO8_D22") (pintype "passive+no_connect"))
    )
    (net (code "251") (name "unconnected-(U5D-GPIO9-PadB22)") (class "Default")
      (node (ref "U5") (pin "B22") (pinfunction "GPIO9_B22") (pintype "passive+no_connect"))
    )
    (net (code "252") (name "unconnected-(U5D-GPIO10-PadC23)") (class "Default")
      (node (ref "U5") (pin "C23") (pinfunction "GPIO10_C23") (pintype "passive+no_connect"))
    )
    (net (code "253") (name "unconnected-(U5D-GPIO11-PadC19)") (class "Default")
      (node (ref "U5") (pin "C19") (pinfunction "GPIO11_C19") (pintype "passive+no_connect"))
    )
    (net (code "254") (name "unconnected-(U5D-GPIO12-PadD19)") (class "Default")
      (node (ref "U5") (pin "D19") (pinfunction "GPIO12_D19") (pintype "passive+no_connect"))
    )
    (net (code "255") (name "unconnected-(U5D-GPIO13-PadAB21)") (class "Default")
      (node (ref "U5") (pin "AB21") (pinfunction "GPIO13_AB21") (pintype "passive+no_connect"))
    )
    (net (code "256") (name "unconnected-(U5D-GPIO14-PadY21)") (class "Default")
      (node (ref "U5") (pin "Y21") (pinfunction "GPIO14_Y21") (pintype "passive+no_connect"))
    )
    (net (code "257") (name "unconnected-(U5D-GPIO15-PadV20)") (class "Default")
      (node (ref "U5") (pin "V20") (pinfunction "GPIO15_V20") (pintype "passive+no_connect"))
    )
    (net (code "258") (name "unconnected-(U5D-GPIO16-PadV21)") (class "Default")
      (node (ref "U5") (pin "V21") (pinfunction "GPIO16_V21") (pintype "passive+no_connect"))
    )
    (net (code "259") (name "unconnected-(U5D-GPIO17-PadAA23)") (class "Default")
      (node (ref "U5") (pin "AA23") (pinfunction "GPIO17_AA23") (pintype "passive+no_connect"))
    )
    (net (code "260") (name "unconnected-(U5D-GPIO_R0-PadE20)") (class "Default")
      (node (ref "U5") (pin "E20") (pinfunction "GPIO_R0_E20") (pintype "passive+no_connect"))
    )
    (net (code "261") (name "unconnected-(U5D-GPIO_R6-PadD21)") (class "Default")
      (node (ref "U5") (pin "D21") (pinfunction "GPIO_R6_D21") (pintype "passive+no_connect"))
    )
    (net (code "262") (name "unconnected-(U5D-GPIO_R7-PadC22)") (class "Default")
      (node (ref "U5") (pin "C22") (pinfunction "GPIO_R7_C22") (pintype "passive+no_connect"))
    )
    (net (code "263") (name "unconnected-(U5D-TACH_IN-PadAC22)") (class "Default")
      (node (ref "U5") (pin "AC22") (pinfunction "TACH_IN_AC22") (pintype "passive+no_connect"))
    )
    (net (code "264") (name "unconnected-(U5D-TDI-PadAC23)") (class "Default")
      (node (ref "U5") (pin "AC23") (pinfunction "TDI_AC23") (pintype "passive+no_connect"))
    )
    (net (code "265") (name "unconnected-(U5D-TMS-PadW21)") (class "Default")
      (node (ref "U5") (pin "W21") (pinfunction "TMS_W21") (pintype "passive+no_connect"))
    )
    (net (code "266") (name "unconnected-(U5D-UART_RX-PadB2)") (class "Default")
      (node (ref "U5") (pin "B2") (pinfunction "UART_RX_B2") (pintype "passive+no_connect"))
    )
    (net (code "267") (name "unconnected-(U5D-V_TEST-PadE21)") (class "Default")
      (node (ref "U5") (pin "E21") (pinfunction "V_TEST_E21") (pintype "passive+no_connect"))
    )
  )
)
